# batsim.net
KiCad netlist of a schematic drawn in EAGLE
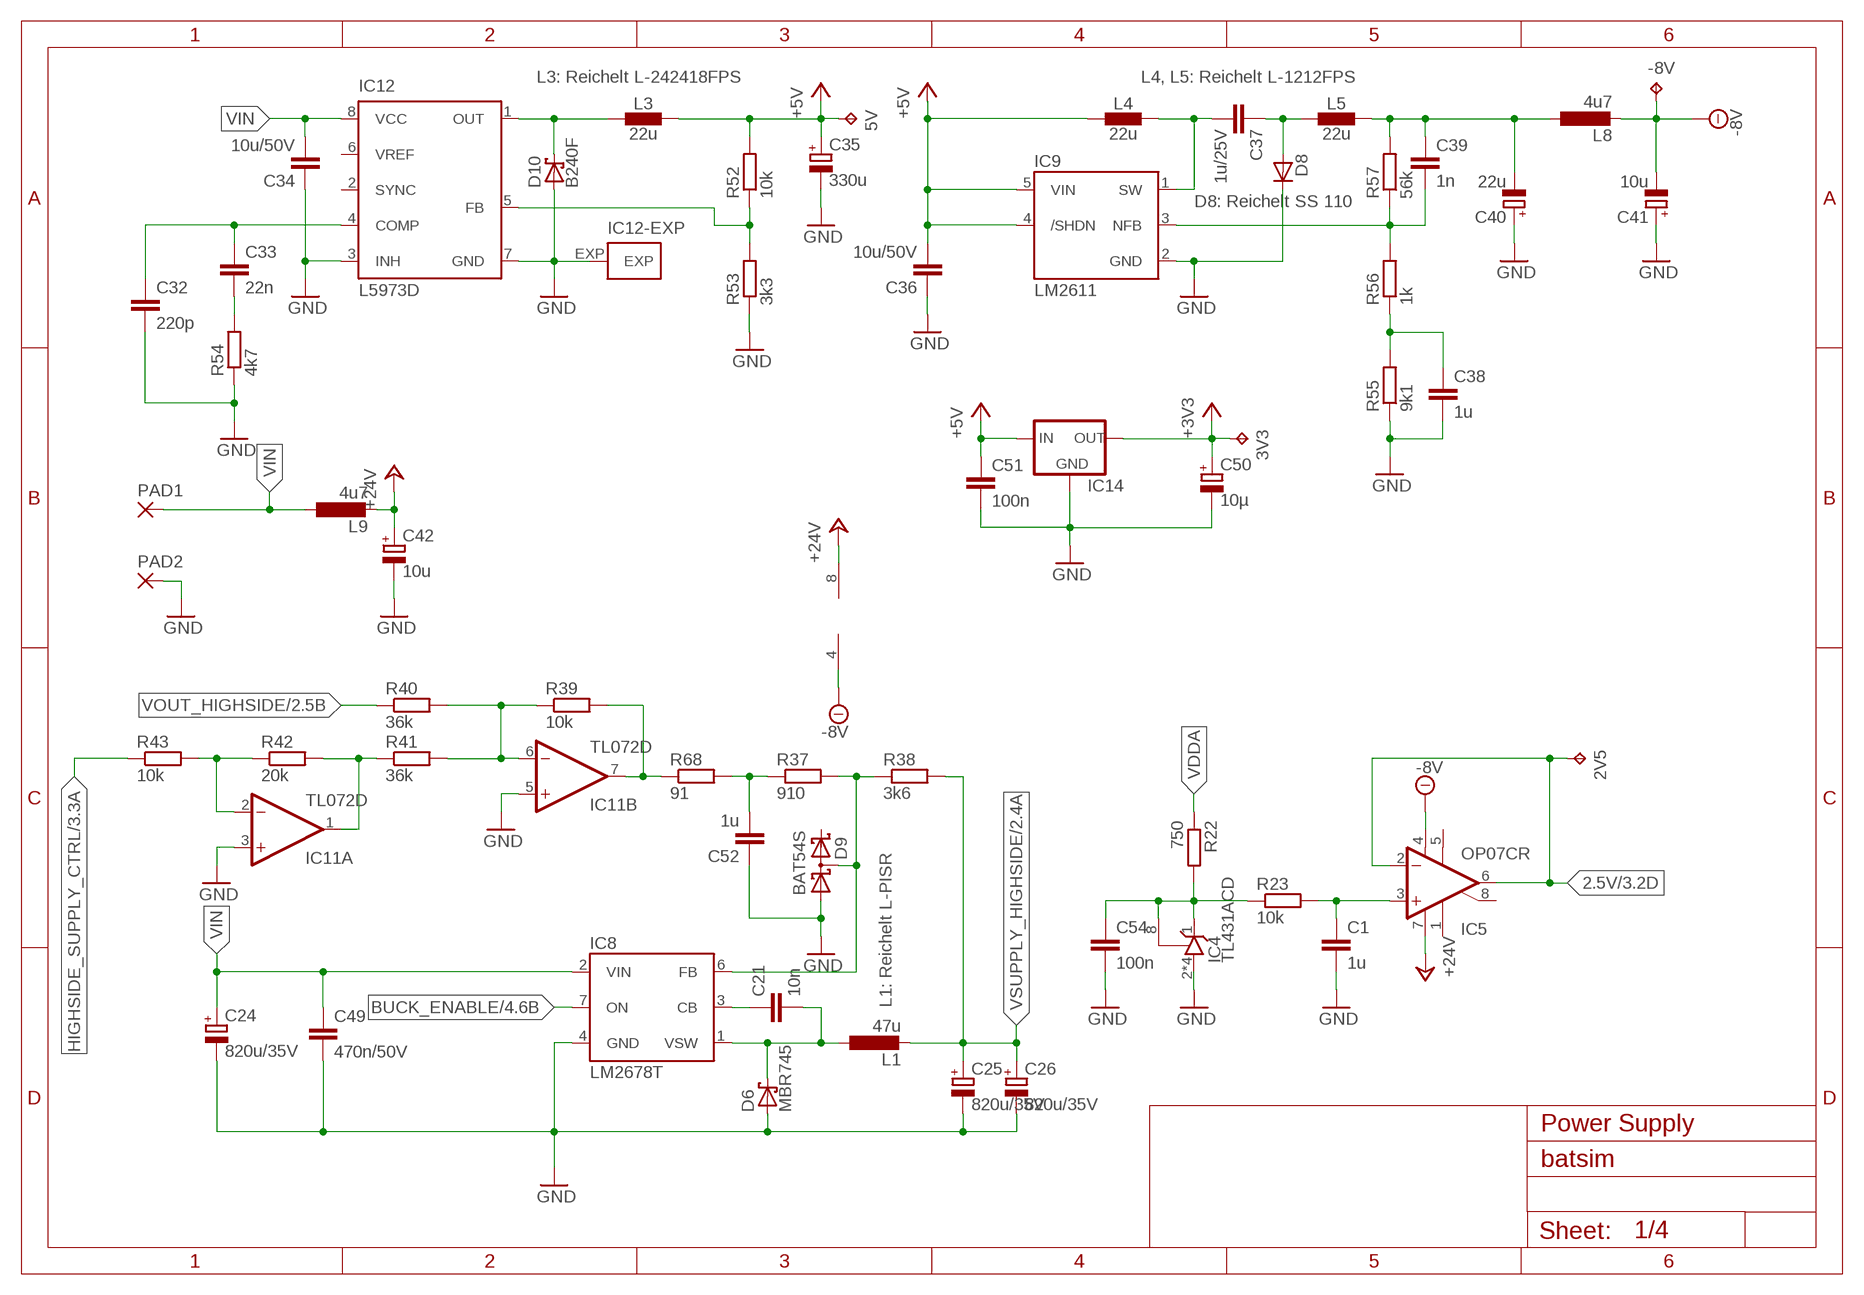
[diagram p0: schematic, sheet 1]
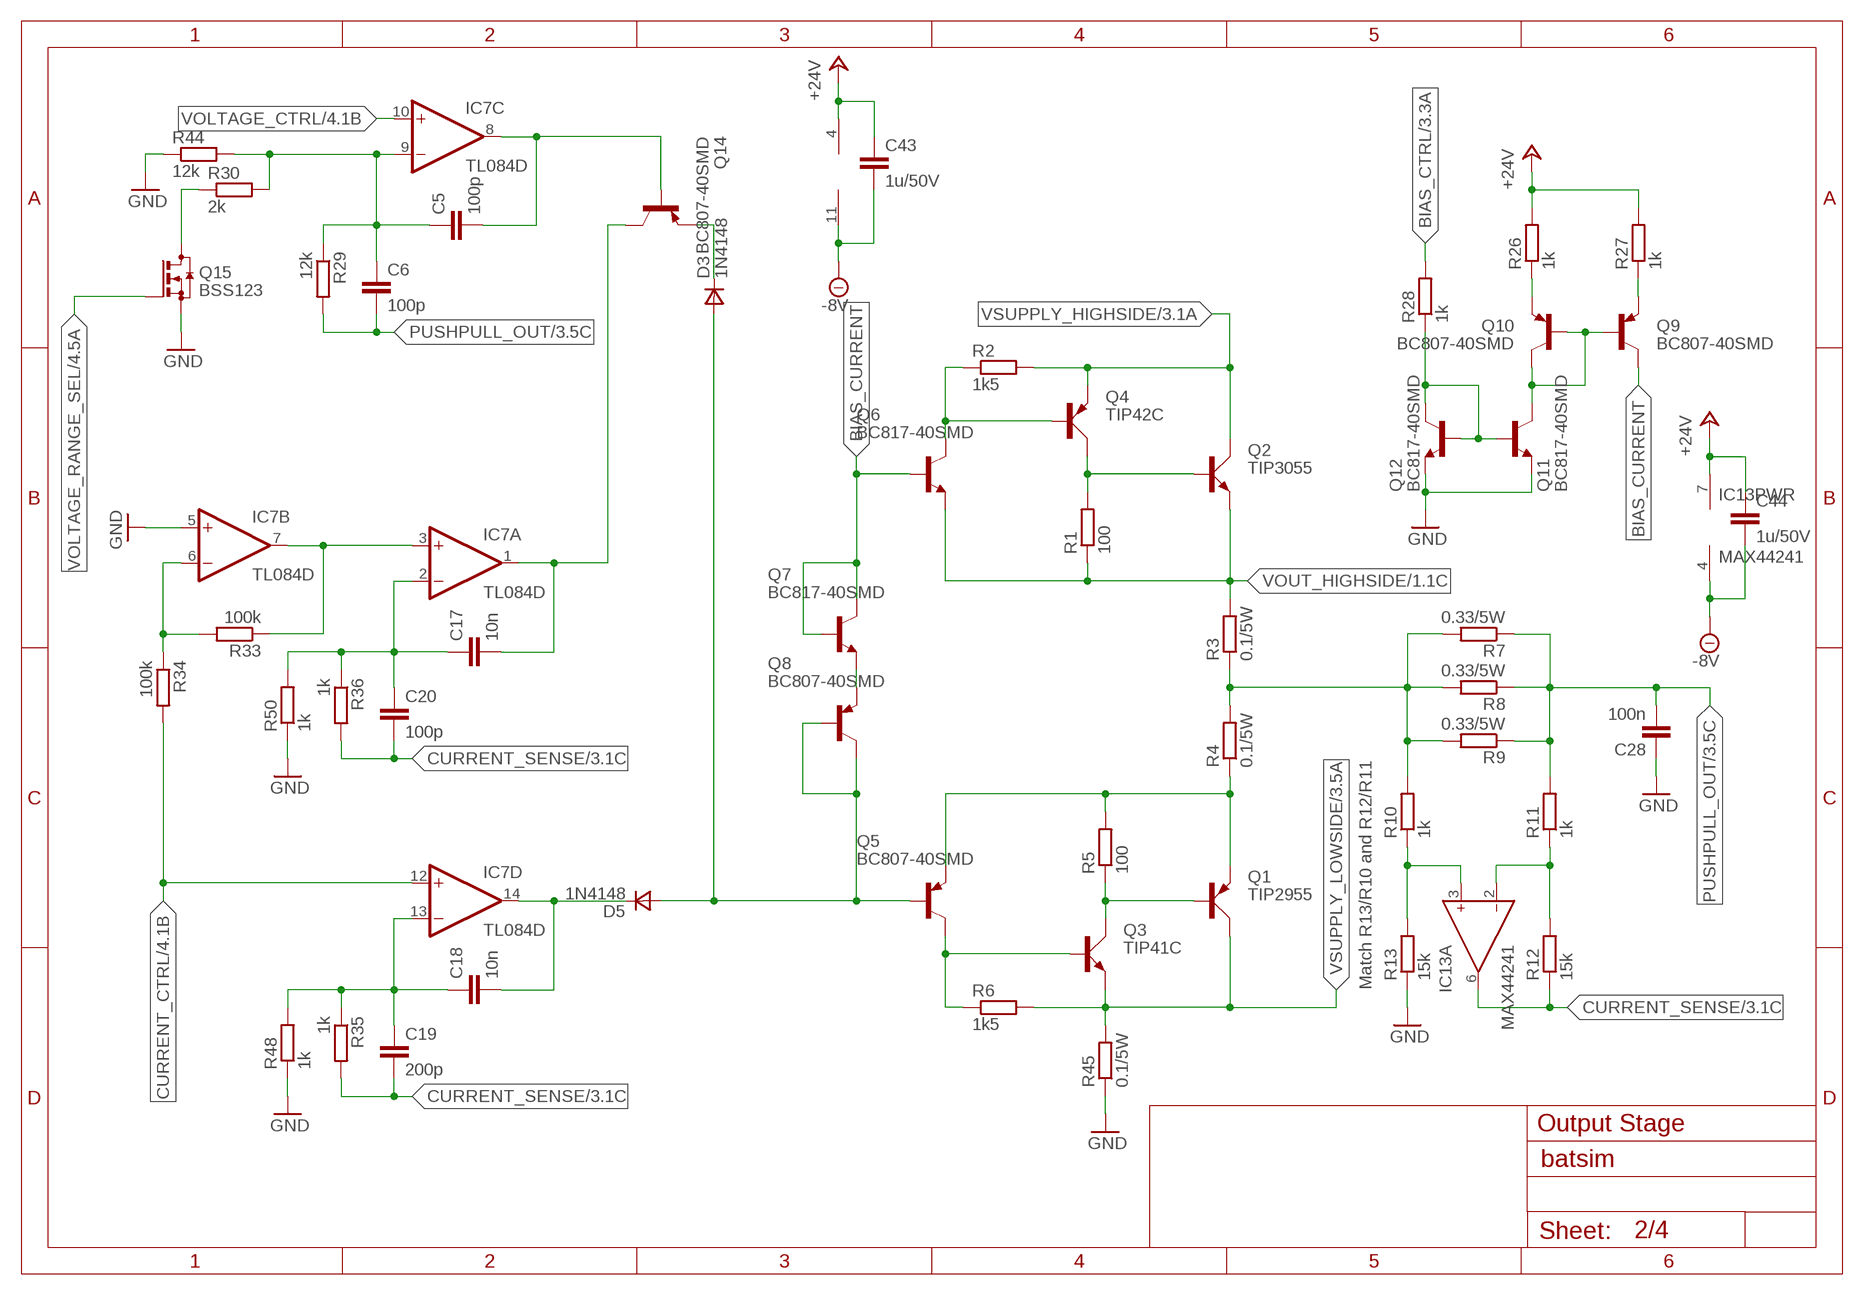
[diagram p1: schematic, sheet 2]
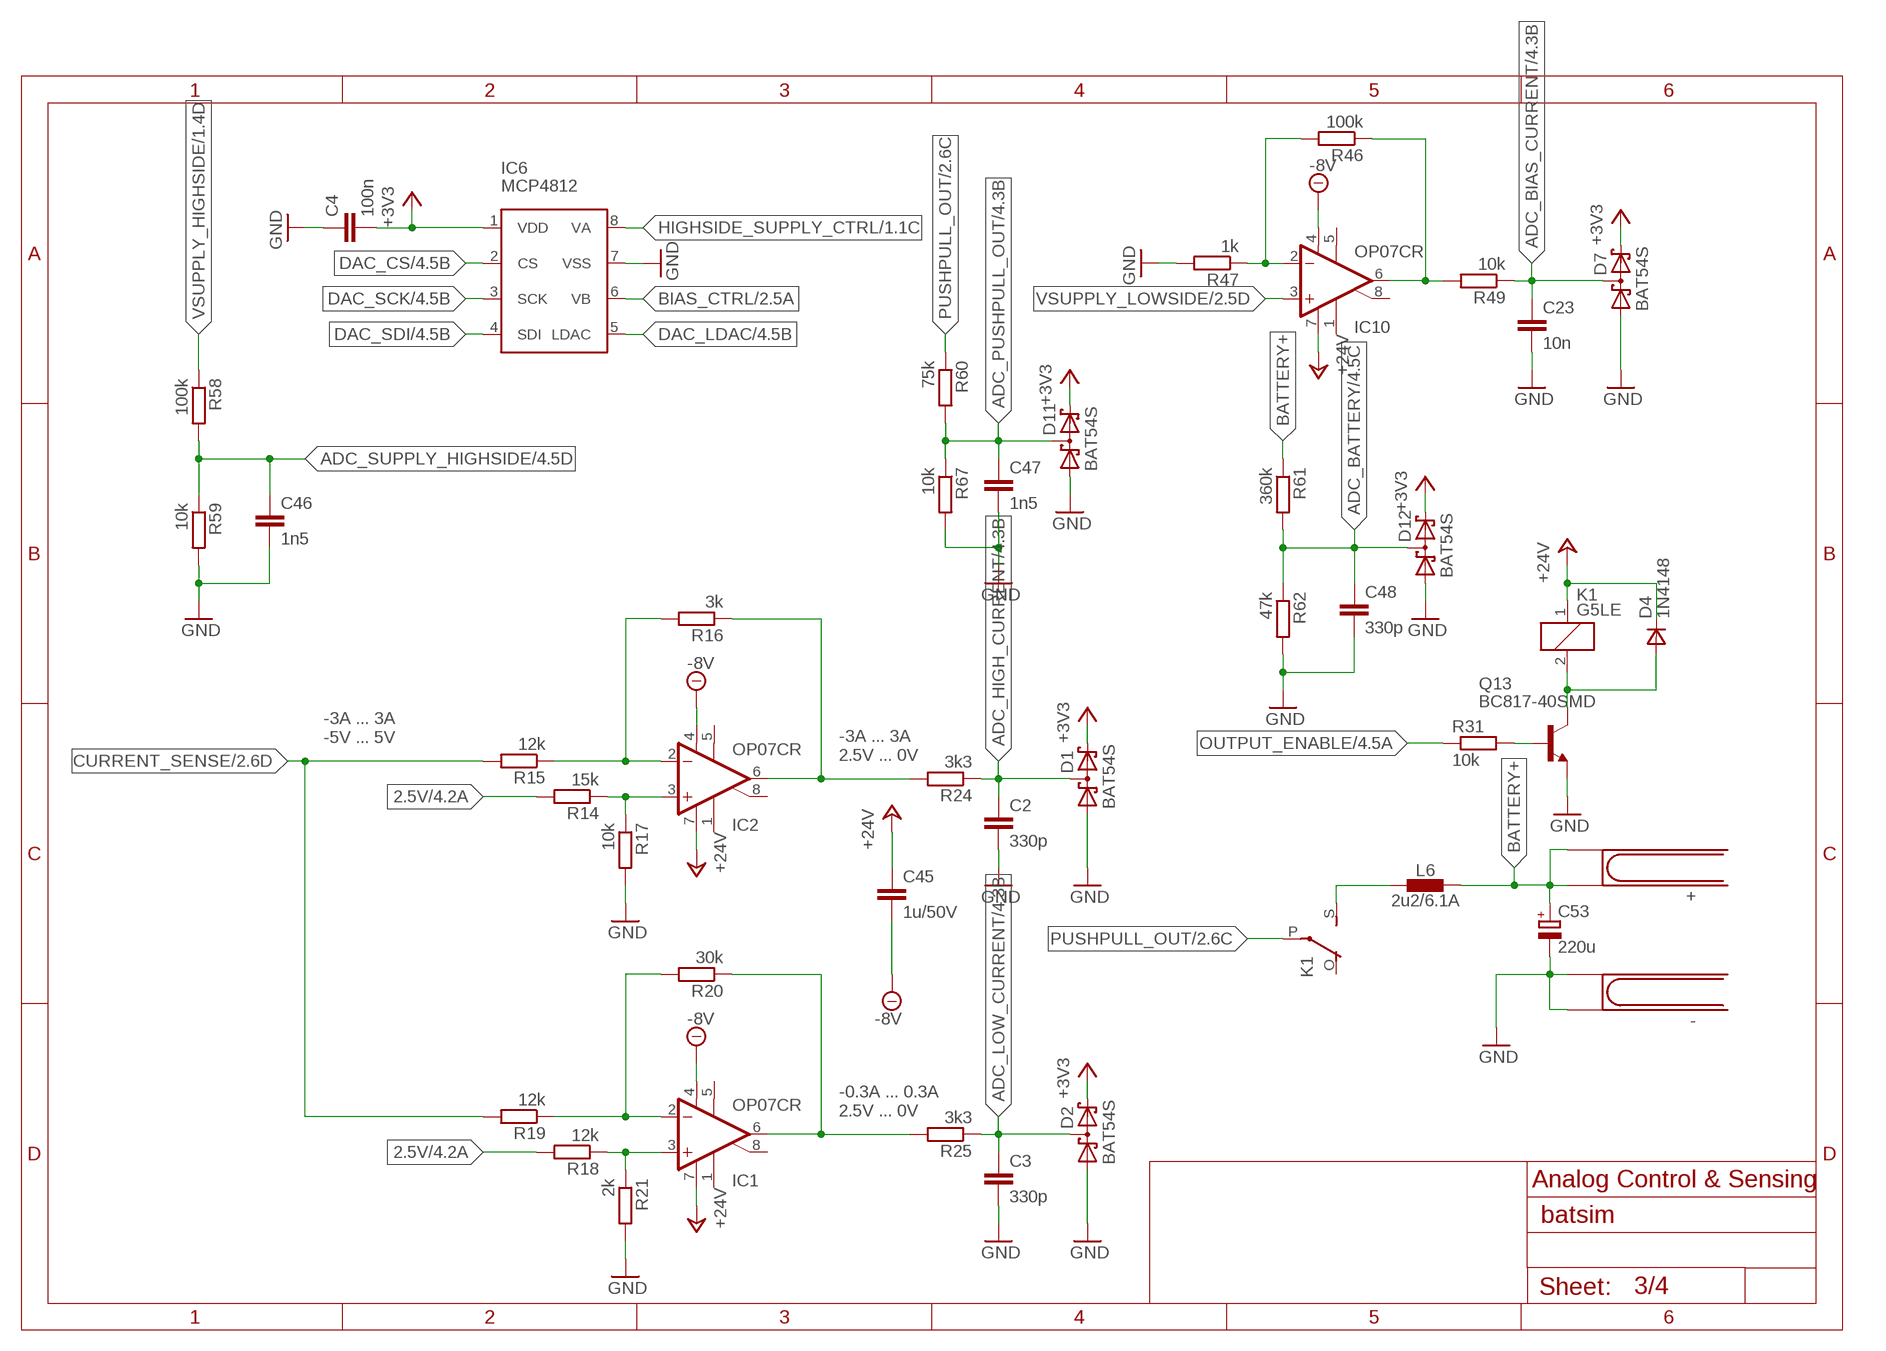
[diagram p2: schematic, sheet 3]
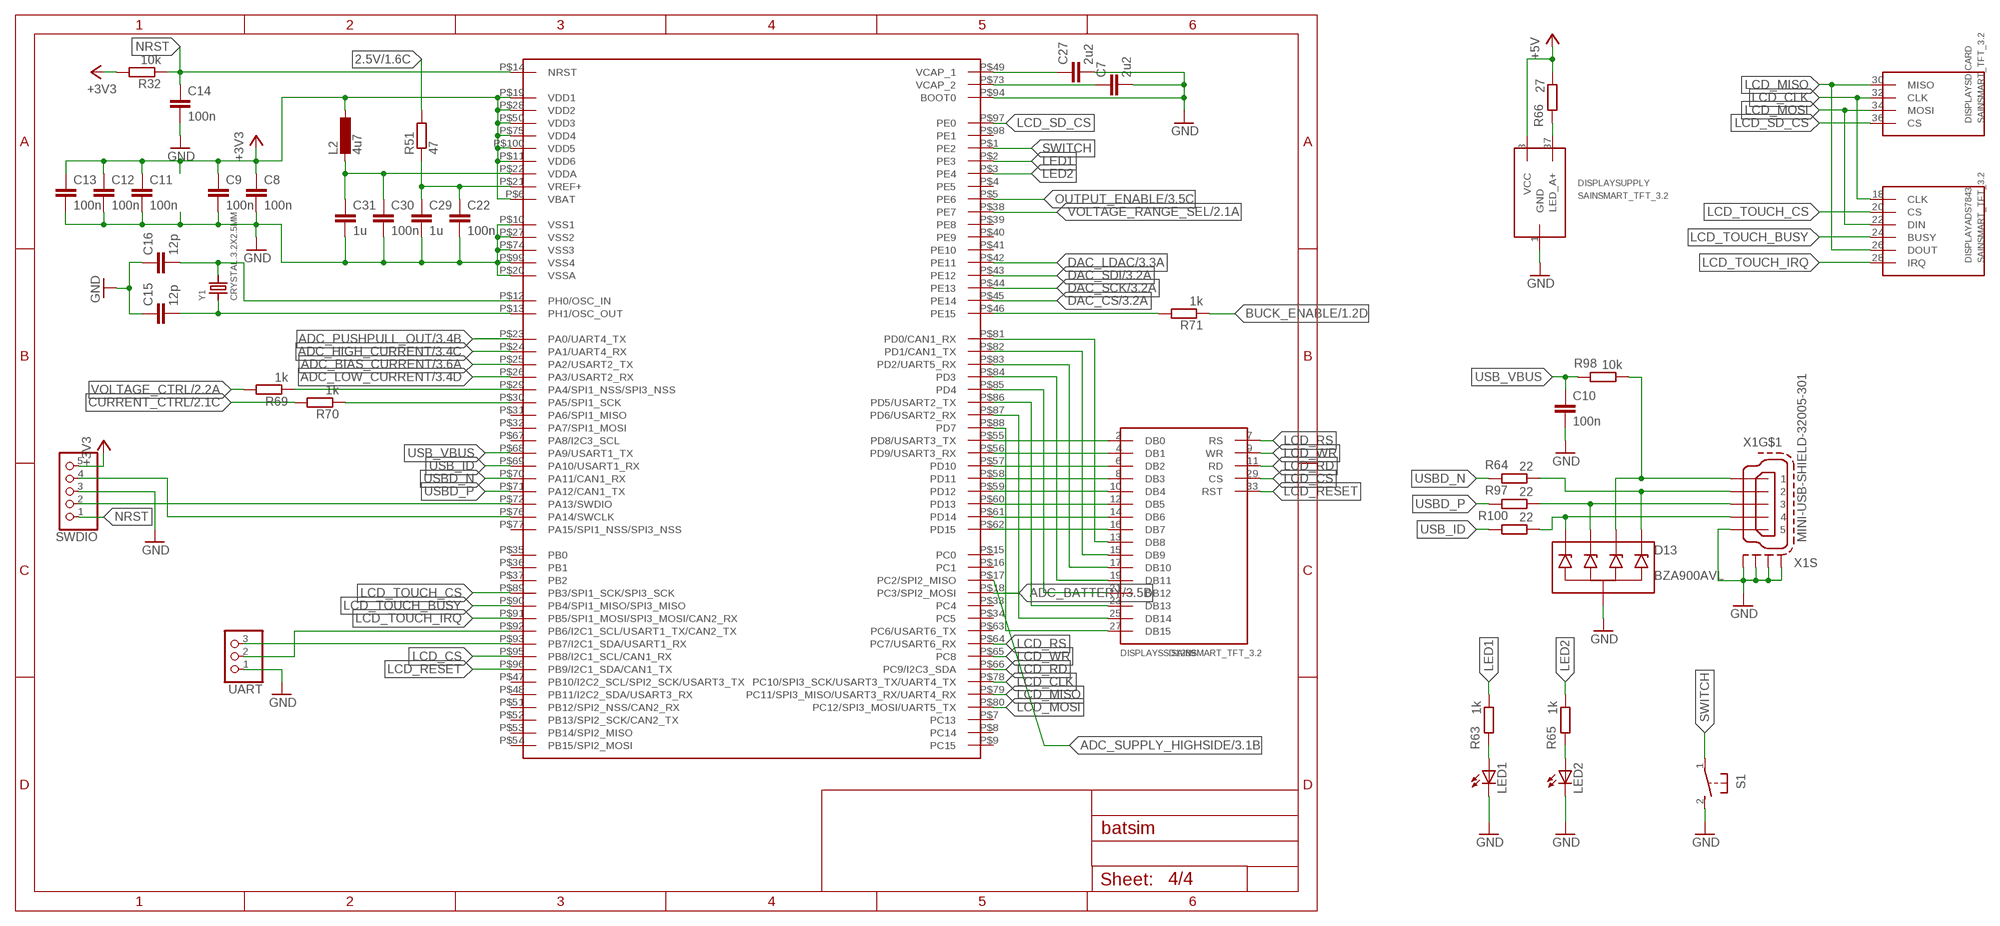
[diagram p3: schematic, sheet 4]

(export (version "E")
  (design (tool "Eeschema 10.0.6"))
  (components
    (comp (ref "C7")
      (value "2u2")
      (footprint "eagle-import:C1206")
      (libsource (lib "eagle-import") (part "C-EUC1206"))
    )
    (comp (ref "C8")
      (value "100n")
      (footprint "eagle-import:C0603")
      (libsource (lib "eagle-import") (part "C-EUC0603"))
    )
    (comp (ref "C9")
      (value "100n")
      (footprint "eagle-import:C0603")
      (libsource (lib "eagle-import") (part "C-EUC0603"))
    )
    (comp (ref "C10")
      (value "100n")
      (footprint "eagle-import:C0603K")
      (libsource (lib "eagle-import") (part "C-EUC0603K"))
    )
    (comp (ref "C11")
      (value "100n")
      (footprint "eagle-import:C0603")
      (libsource (lib "eagle-import") (part "C-EUC0603"))
    )
    (comp (ref "C12")
      (value "100n")
      (footprint "eagle-import:C0603")
      (libsource (lib "eagle-import") (part "C-EUC0603"))
    )
    (comp (ref "C13")
      (value "100n")
      (footprint "eagle-import:C0603")
      (libsource (lib "eagle-import") (part "C-EUC0603"))
    )
    (comp (ref "C14")
      (value "100n")
      (footprint "eagle-import:C0603")
      (libsource (lib "eagle-import") (part "C-EUC0603"))
    )
    (comp (ref "C15")
      (value "12p")
      (footprint "eagle-import:C0603")
      (libsource (lib "eagle-import") (part "C-EUC0603"))
    )
    (comp (ref "C16")
      (value "12p")
      (footprint "eagle-import:C0603")
      (libsource (lib "eagle-import") (part "C-EUC0603"))
    )
    (comp (ref "C22")
      (value "100n")
      (footprint "eagle-import:C0603")
      (libsource (lib "eagle-import") (part "C-EUC0603"))
    )
    (comp (ref "C27")
      (value "2u2")
      (footprint "eagle-import:C1206")
      (libsource (lib "eagle-import") (part "C-EUC1206"))
    )
    (comp (ref "C29")
      (value "1u")
      (footprint "eagle-import:C0603")
      (libsource (lib "eagle-import") (part "C-EUC0603"))
    )
    (comp (ref "C30")
      (value "100n")
      (footprint "eagle-import:C0603")
      (libsource (lib "eagle-import") (part "C-EUC0603"))
    )
    (comp (ref "C31")
      (value "1u")
      (footprint "eagle-import:C0603")
      (libsource (lib "eagle-import") (part "C-EUC0603"))
    )
    (comp (ref "D13")
      (value "BZA900AVL")
      (footprint "eagle-import:SOT-665")
      (libsource (lib "eagle-import") (part "BZA900AVL"))
    )
    (comp (ref "DISPLAY")
      (value "SAINSMART_TFT_3.2")
      (footprint "eagle-import:SAINSMART_TFT_3.2")
      (libsource (lib "eagle-import") (part "SAINSMART_TFT_3.2"))
    )
    (comp (ref "L2")
      (value "4u7")
      (footprint "eagle-import:L2012C")
      (libsource (lib "eagle-import") (part "L-EUL2012C"))
    )
    (comp (ref "LED1")
      (value "LEDCHIP-LED0603")
      (footprint "eagle-import:CHIP-LED0603")
      (libsource (lib "eagle-import") (part "LEDCHIP-LED0603"))
    )
    (comp (ref "LED2")
      (value "LEDCHIP-LED0603")
      (footprint "eagle-import:CHIP-LED0603")
      (libsource (lib "eagle-import") (part "LEDCHIP-LED0603"))
    )
    (comp (ref "R32")
      (value "10k")
      (footprint "eagle-import:R0603")
      (libsource (lib "eagle-import") (part "R-EU_R0603"))
    )
    (comp (ref "R51")
      (value "47")
      (footprint "eagle-import:R0603")
      (libsource (lib "eagle-import") (part "R-EU_R0603"))
    )
    (comp (ref "R63")
      (value "1k")
      (footprint "eagle-import:R0603")
      (libsource (lib "eagle-import") (part "R-EU_R0603"))
    )
    (comp (ref "R64")
      (value "22")
      (footprint "eagle-import:R0603")
      (libsource (lib "eagle-import") (part "R-EU_R0603"))
    )
    (comp (ref "R65")
      (value "1k")
      (footprint "eagle-import:R0603")
      (libsource (lib "eagle-import") (part "R-EU_R0603"))
    )
    (comp (ref "R66")
      (value "27")
      (footprint "eagle-import:R0603")
      (libsource (lib "eagle-import") (part "R-EU_R0603"))
    )
    (comp (ref "R69")
      (value "1k")
      (footprint "eagle-import:R0603")
      (libsource (lib "eagle-import") (part "R-EU_R0603"))
    )
    (comp (ref "R70")
      (value "1k")
      (footprint "eagle-import:R0603")
      (libsource (lib "eagle-import") (part "R-EU_R0603"))
    )
    (comp (ref "R71")
      (value "1k")
      (footprint "eagle-import:R0603")
      (libsource (lib "eagle-import") (part "R-EU_R0603"))
    )
    (comp (ref "R97")
      (value "22")
      (footprint "eagle-import:R0603")
      (libsource (lib "eagle-import") (part "R-EU_R0603"))
    )
    (comp (ref "R98")
      (value "10k")
      (footprint "eagle-import:R0603")
      (libsource (lib "eagle-import") (part "R-EU_R0603"))
    )
    (comp (ref "R100")
      (value "22")
      (footprint "eagle-import:R0603")
      (libsource (lib "eagle-import") (part "R-EU_R0603"))
    )
    (comp (ref "S1")
      (value "31-XX")
      (footprint "eagle-import:B3F-31XX")
      (fields (field (name "MPN") "B3F-3100"))
      (libsource (lib "eagle-import") (part "31-XX"))
    )
    (comp (ref "SWDIO")
      (value "PINHD-1X5")
      (footprint "eagle-import:1X05")
      (libsource (lib "eagle-import") (part "PINHD-1X5"))
    )
    (comp (ref "U$1")
      (value "STM32F407X100")
      (footprint "eagle-import:LQFP100_14")
      (libsource (lib "eagle-import") (part "STM32F407X100"))
    )
    (comp (ref "UART")
      (value "PINHD-1X3")
      (footprint "eagle-import:1X03")
      (libsource (lib "eagle-import") (part "PINHD-1X3"))
    )
    (comp (ref "X1")
      (value "MINI-USB-SHIELD-32005-301")
      (footprint "eagle-import:32005-301")
      (libsource (lib "eagle-import") (part "MINI-USB-SCHIELD-32005-301"))
    )
    (comp (ref "Y1")
      (value "CRYSTAL.3.2X2.5MM")
      (footprint "eagle-import:3.2X2.5MM")
      (libsource (lib "eagle-import") (part "CRYSTAL.3.2X2.5MM"))
    )
    (comp (ref "C5")
      (value "100p")
      (footprint "eagle-import:C0603")
      (libsource (lib "eagle-import") (part "C-EUC0603"))
    )
    (comp (ref "C6")
      (value "100p")
      (footprint "eagle-import:C0603")
      (libsource (lib "eagle-import") (part "C-EUC0603"))
    )
    (comp (ref "C17")
      (value "10n")
      (footprint "eagle-import:C0603")
      (libsource (lib "eagle-import") (part "C-EUC0603"))
    )
    (comp (ref "C18")
      (value "10n")
      (footprint "eagle-import:C0603")
      (libsource (lib "eagle-import") (part "C-EUC0603"))
    )
    (comp (ref "C19")
      (value "200p")
      (footprint "eagle-import:C0603")
      (libsource (lib "eagle-import") (part "C-EUC0603"))
    )
    (comp (ref "C20")
      (value "100p")
      (footprint "eagle-import:C0603")
      (libsource (lib "eagle-import") (part "C-EUC0603"))
    )
    (comp (ref "C28")
      (value "100n")
      (footprint "eagle-import:C1206")
      (libsource (lib "eagle-import") (part "C-EUC1206"))
    )
    (comp (ref "C43")
      (value "1u/50V")
      (footprint "eagle-import:C0603")
      (libsource (lib "eagle-import") (part "C-EUC0603"))
    )
    (comp (ref "C44")
      (value "1u/50V")
      (footprint "eagle-import:C0603")
      (libsource (lib "eagle-import") (part "C-EUC0603"))
    )
    (comp (ref "D3")
      (value "1N4148")
      (footprint "eagle-import:SOD323")
      (fields (field (name "MPN") "CDSOD323-T05C"))
      (libsource (lib "eagle-import") (part "DSOD323"))
    )
    (comp (ref "D5")
      (value "1N4148")
      (footprint "eagle-import:SOD323")
      (fields (field (name "MPN") "CDSOD323-T05C"))
      (libsource (lib "eagle-import") (part "DSOD323"))
    )
    (comp (ref "IC7")
      (value "TL084D")
      (footprint "eagle-import:SO14")
      (libsource (lib "eagle-import") (part "TL084D"))
    )
    (comp (ref "IC13")
      (value "MAX44241")
      (footprint "eagle-import:UMAX8")
      (libsource (lib "eagle-import") (part "MAX44241"))
    )
    (comp (ref "Q1")
      (value "TIP2955")
      (footprint "eagle-import:TOP3AV")
      (libsource (lib "eagle-import") (part "TIP2955"))
    )
    (comp (ref "Q2")
      (value "TIP3055")
      (footprint "eagle-import:TOP3AV")
      (libsource (lib "eagle-import") (part "TIP3055"))
    )
    (comp (ref "Q3")
      (value "TIP41C")
      (footprint "eagle-import:TO220AV")
      (libsource (lib "eagle-import") (part "TIP41C"))
    )
    (comp (ref "Q4")
      (value "TIP42C")
      (footprint "eagle-import:TO220AV")
      (libsource (lib "eagle-import") (part "TIP42C"))
    )
    (comp (ref "Q5")
      (value "BC807-40SMD")
      (footprint "eagle-import:SOT23-BEC")
      (libsource (lib "eagle-import") (part "BC807SMD-40"))
    )
    (comp (ref "Q6")
      (value "BC817-40SMD")
      (footprint "eagle-import:SOT23-BEC")
      (libsource (lib "eagle-import") (part "BC817SMD-40"))
    )
    (comp (ref "Q7")
      (value "BC817-40SMD")
      (footprint "eagle-import:SOT23-BEC")
      (libsource (lib "eagle-import") (part "BC817SMD-40"))
    )
    (comp (ref "Q8")
      (value "BC807-40SMD")
      (footprint "eagle-import:SOT23-BEC")
      (libsource (lib "eagle-import") (part "BC807SMD-40"))
    )
    (comp (ref "Q9")
      (value "BC807-40SMD")
      (footprint "eagle-import:SOT23-BEC")
      (libsource (lib "eagle-import") (part "BC807SMD-40"))
    )
    (comp (ref "Q10")
      (value "BC807-40SMD")
      (footprint "eagle-import:SOT23-BEC")
      (libsource (lib "eagle-import") (part "BC807SMD-40"))
    )
    (comp (ref "Q11")
      (value "BC817-40SMD")
      (footprint "eagle-import:SOT23-BEC")
      (libsource (lib "eagle-import") (part "BC817SMD-40"))
    )
    (comp (ref "Q12")
      (value "BC817-40SMD")
      (footprint "eagle-import:SOT23-BEC")
      (libsource (lib "eagle-import") (part "BC817SMD-40"))
    )
    (comp (ref "Q14")
      (value "BC807-40SMD")
      (footprint "eagle-import:SOT23-BEC")
      (libsource (lib "eagle-import") (part "BC807SMD-40"))
    )
    (comp (ref "Q15")
      (value "BSS123")
      (footprint "eagle-import:SOT23")
      (libsource (lib "eagle-import") (part "BSS123"))
    )
    (comp (ref "R1")
      (value "100")
      (footprint "eagle-import:R0603")
      (libsource (lib "eagle-import") (part "R-EU_R0603"))
    )
    (comp (ref "R2")
      (value "1k5")
      (footprint "eagle-import:R0603")
      (libsource (lib "eagle-import") (part "R-EU_R0603"))
    )
    (comp (ref "R3")
      (value "0.1/5W")
      (footprint "eagle-import:5WAXIAL")
      (libsource (lib "eagle-import") (part "5WAXIAL"))
    )
    (comp (ref "R4")
      (value "0.1/5W")
      (footprint "eagle-import:5WAXIAL")
      (libsource (lib "eagle-import") (part "5WAXIAL"))
    )
    (comp (ref "R5")
      (value "100")
      (footprint "eagle-import:R0603")
      (libsource (lib "eagle-import") (part "R-EU_R0603"))
    )
    (comp (ref "R6")
      (value "1k5")
      (footprint "eagle-import:R0603")
      (libsource (lib "eagle-import") (part "R-EU_R0603"))
    )
    (comp (ref "R7")
      (value "0.33/5W")
      (footprint "eagle-import:5WAXIAL")
      (libsource (lib "eagle-import") (part "5WAXIAL"))
    )
    (comp (ref "R8")
      (value "0.33/5W")
      (footprint "eagle-import:5WAXIAL")
      (libsource (lib "eagle-import") (part "5WAXIAL"))
    )
    (comp (ref "R9")
      (value "0.33/5W")
      (footprint "eagle-import:5WAXIAL")
      (libsource (lib "eagle-import") (part "5WAXIAL"))
    )
    (comp (ref "R10")
      (value "1k")
      (footprint "eagle-import:R0603")
      (libsource (lib "eagle-import") (part "R-EU_R0603"))
    )
    (comp (ref "R11")
      (value "1k")
      (footprint "eagle-import:R0603")
      (libsource (lib "eagle-import") (part "R-EU_R0603"))
    )
    (comp (ref "R12")
      (value "15k")
      (footprint "eagle-import:R0603")
      (libsource (lib "eagle-import") (part "R-EU_R0603"))
    )
    (comp (ref "R13")
      (value "15k")
      (footprint "eagle-import:R0603")
      (libsource (lib "eagle-import") (part "R-EU_R0603"))
    )
    (comp (ref "R26")
      (value "1k")
      (footprint "eagle-import:R0603")
      (libsource (lib "eagle-import") (part "R-EU_R0603"))
    )
    (comp (ref "R27")
      (value "1k")
      (footprint "eagle-import:R0603")
      (libsource (lib "eagle-import") (part "R-EU_R0603"))
    )
    (comp (ref "R28")
      (value "1k")
      (footprint "eagle-import:R0603")
      (libsource (lib "eagle-import") (part "R-EU_R0603"))
    )
    (comp (ref "R29")
      (value "12k")
      (footprint "eagle-import:R0603")
      (libsource (lib "eagle-import") (part "R-EU_R0603"))
    )
    (comp (ref "R30")
      (value "2k")
      (footprint "eagle-import:R0603")
      (libsource (lib "eagle-import") (part "R-EU_R0603"))
    )
    (comp (ref "R33")
      (value "100k")
      (footprint "eagle-import:R0603")
      (libsource (lib "eagle-import") (part "R-EU_R0603"))
    )
    (comp (ref "R34")
      (value "100k")
      (footprint "eagle-import:R0603")
      (libsource (lib "eagle-import") (part "R-EU_R0603"))
    )
    (comp (ref "R35")
      (value "1k")
      (footprint "eagle-import:R0603")
      (libsource (lib "eagle-import") (part "R-EU_R0603"))
    )
    (comp (ref "R36")
      (value "1k")
      (footprint "eagle-import:R0603")
      (libsource (lib "eagle-import") (part "R-EU_R0603"))
    )
    (comp (ref "R44")
      (value "12k")
      (footprint "eagle-import:R0603")
      (libsource (lib "eagle-import") (part "R-EU_R0603"))
    )
    (comp (ref "R45")
      (value "0.1/5W")
      (footprint "eagle-import:5WAXIAL")
      (libsource (lib "eagle-import") (part "5WAXIAL"))
    )
    (comp (ref "R48")
      (value "1k")
      (footprint "eagle-import:R0603")
      (libsource (lib "eagle-import") (part "R-EU_R0603"))
    )
    (comp (ref "R50")
      (value "1k")
      (footprint "eagle-import:R0603")
      (libsource (lib "eagle-import") (part "R-EU_R0603"))
    )
    (comp (ref "+")
      (value "4MMJACK")
      (footprint "eagle-import:4MMJACK")
      (libsource (lib "eagle-import") (part "4MMJACK"))
    )
    (comp (ref "-")
      (value "4MMJACK")
      (footprint "eagle-import:4MMJACK")
      (libsource (lib "eagle-import") (part "4MMJACK"))
    )
    (comp (ref "C2")
      (value "330p")
      (footprint "eagle-import:C0603")
      (libsource (lib "eagle-import") (part "C-EUC0603"))
    )
    (comp (ref "C3")
      (value "330p")
      (footprint "eagle-import:C0603")
      (libsource (lib "eagle-import") (part "C-EUC0603"))
    )
    (comp (ref "C4")
      (value "100n")
      (footprint "eagle-import:C0603")
      (libsource (lib "eagle-import") (part "C-EUC0603"))
    )
    (comp (ref "C23")
      (value "10n")
      (footprint "eagle-import:C0603")
      (libsource (lib "eagle-import") (part "C-EUC0603"))
    )
    (comp (ref "C45")
      (value "1u/50V")
      (footprint "eagle-import:C0603")
      (libsource (lib "eagle-import") (part "C-EUC0603"))
    )
    (comp (ref "C46")
      (value "1n5")
      (footprint "eagle-import:C0603")
      (libsource (lib "eagle-import") (part "C-EUC0603"))
    )
    (comp (ref "C47")
      (value "1n5")
      (footprint "eagle-import:C0603")
      (libsource (lib "eagle-import") (part "C-EUC0603"))
    )
    (comp (ref "C48")
      (value "330p")
      (footprint "eagle-import:C0603")
      (libsource (lib "eagle-import") (part "C-EUC0603"))
    )
    (comp (ref "C53")
      (value "220u")
      (footprint "eagle-import:E5-10,5")
      (libsource (lib "eagle-import") (part "resistor_CPOL-EUE5-10.5"))
    )
    (comp (ref "D1")
      (value "BAT54S")
      (footprint "eagle-import:SOT23")
      (libsource (lib "eagle-import") (part "BAT54S"))
    )
    (comp (ref "D2")
      (value "BAT54S")
      (footprint "eagle-import:SOT23")
      (libsource (lib "eagle-import") (part "BAT54S"))
    )
    (comp (ref "D4")
      (value "1N4148")
      (footprint "eagle-import:SOD323")
      (fields (field (name "MPN") "CDSOD323-T05C"))
      (libsource (lib "eagle-import") (part "DSOD323"))
    )
    (comp (ref "D7")
      (value "BAT54S")
      (footprint "eagle-import:SOT23")
      (libsource (lib "eagle-import") (part "BAT54S"))
    )
    (comp (ref "D11")
      (value "BAT54S")
      (footprint "eagle-import:SOT23")
      (libsource (lib "eagle-import") (part "BAT54S"))
    )
    (comp (ref "D12")
      (value "BAT54S")
      (footprint "eagle-import:SOT23")
      (libsource (lib "eagle-import") (part "BAT54S"))
    )
    (comp (ref "IC1")
      (value "OP07CR")
      (footprint "eagle-import:SO08")
      (libsource (lib "eagle-import") (part "OP07RC"))
    )
    (comp (ref "IC2")
      (value "OP07CR")
      (footprint "eagle-import:SO08")
      (libsource (lib "eagle-import") (part "OP07RC"))
    )
    (comp (ref "IC6")
      (value "MCP4812")
      (footprint "eagle-import:SO08")
      (fields (field (name "MPN") "MCP4822-E/SN"))
      (libsource (lib "eagle-import") (part "MCP4812"))
    )
    (comp (ref "IC10")
      (value "OP07CR")
      (footprint "eagle-import:SO08")
      (libsource (lib "eagle-import") (part "OP07RC"))
    )
    (comp (ref "K1")
      (value "G5LE")
      (footprint "eagle-import:G5LE")
      (libsource (lib "eagle-import") (part "G5LE"))
    )
    (comp (ref "L6")
      (value "2u2/6.1A")
      (footprint "eagle-import:L_NR60XX")
      (libsource (lib "eagle-import") (part "INDUCTOR-NR60XX"))
    )
    (comp (ref "Q13")
      (value "BC817-40SMD")
      (footprint "eagle-import:SOT23-BEC")
      (libsource (lib "eagle-import") (part "BC817SMD-40"))
    )
    (comp (ref "R14")
      (value "15k")
      (footprint "eagle-import:R0603")
      (libsource (lib "eagle-import") (part "R-EU_R0603"))
    )
    (comp (ref "R15")
      (value "12k")
      (footprint "eagle-import:R0603")
      (libsource (lib "eagle-import") (part "R-EU_R0603"))
    )
    (comp (ref "R16")
      (value "3k")
      (footprint "eagle-import:R0603")
      (libsource (lib "eagle-import") (part "R-EU_R0603"))
    )
    (comp (ref "R17")
      (value "10k")
      (footprint "eagle-import:R0603")
      (libsource (lib "eagle-import") (part "R-EU_R0603"))
    )
    (comp (ref "R18")
      (value "12k")
      (footprint "eagle-import:R0603")
      (libsource (lib "eagle-import") (part "R-EU_R0603"))
    )
    (comp (ref "R19")
      (value "12k")
      (footprint "eagle-import:R0603")
      (libsource (lib "eagle-import") (part "R-EU_R0603"))
    )
    (comp (ref "R20")
      (value "30k")
      (footprint "eagle-import:R0603")
      (libsource (lib "eagle-import") (part "R-EU_R0603"))
    )
    (comp (ref "R21")
      (value "2k")
      (footprint "eagle-import:R0603")
      (libsource (lib "eagle-import") (part "R-EU_R0603"))
    )
    (comp (ref "R24")
      (value "3k3")
      (footprint "eagle-import:R0603")
      (libsource (lib "eagle-import") (part "R-EU_R0603"))
    )
    (comp (ref "R25")
      (value "3k3")
      (footprint "eagle-import:R0603")
      (libsource (lib "eagle-import") (part "R-EU_R0603"))
    )
    (comp (ref "R31")
      (value "10k")
      (footprint "eagle-import:R0603")
      (libsource (lib "eagle-import") (part "R-EU_R0603"))
    )
    (comp (ref "R46")
      (value "100k")
      (footprint "eagle-import:R0603")
      (libsource (lib "eagle-import") (part "R-EU_R0603"))
    )
    (comp (ref "R47")
      (value "1k")
      (footprint "eagle-import:R0603")
      (libsource (lib "eagle-import") (part "R-EU_R0603"))
    )
    (comp (ref "R49")
      (value "10k")
      (footprint "eagle-import:R0603")
      (libsource (lib "eagle-import") (part "R-EU_R0603"))
    )
    (comp (ref "R58")
      (value "100k")
      (footprint "eagle-import:R0603")
      (libsource (lib "eagle-import") (part "R-EU_R0603"))
    )
    (comp (ref "R59")
      (value "10k")
      (footprint "eagle-import:R0603")
      (libsource (lib "eagle-import") (part "R-EU_R0603"))
    )
    (comp (ref "R60")
      (value "75k")
      (footprint "eagle-import:R0603")
      (libsource (lib "eagle-import") (part "R-EU_R0603"))
    )
    (comp (ref "R61")
      (value "360k")
      (footprint "eagle-import:R0603")
      (libsource (lib "eagle-import") (part "R-EU_R0603"))
    )
    (comp (ref "R62")
      (value "47k")
      (footprint "eagle-import:R0603")
      (libsource (lib "eagle-import") (part "R-EU_R0603"))
    )
    (comp (ref "R67")
      (value "10k")
      (footprint "eagle-import:R0603")
      (libsource (lib "eagle-import") (part "R-EU_R0603"))
    )
    (comp (ref "-8V")
      (value "TPB1,27")
      (footprint "eagle-import:B1,27")
      (libsource (lib "eagle-import") (part "TPB1,27"))
    )
    (comp (ref "2V5")
      (value "TPB1,27")
      (footprint "eagle-import:B1,27")
      (libsource (lib "eagle-import") (part "TPB1,27"))
    )
    (comp (ref "3V3")
      (value "TPB1,27")
      (footprint "eagle-import:B1,27")
      (libsource (lib "eagle-import") (part "TPB1,27"))
    )
    (comp (ref "5V")
      (value "TPB1,27")
      (footprint "eagle-import:B1,27")
      (libsource (lib "eagle-import") (part "TPB1,27"))
    )
    (comp (ref "C1")
      (value "1u")
      (footprint "eagle-import:C0603")
      (libsource (lib "eagle-import") (part "C-EUC0603"))
    )
    (comp (ref "C21")
      (value "10n")
      (footprint "eagle-import:C0603")
      (libsource (lib "eagle-import") (part "C-EUC0603"))
    )
    (comp (ref "C24")
      (value "820u/35V")
      (footprint "eagle-import:E5-10,5")
      (libsource (lib "eagle-import") (part "resistor_CPOL-EUE5-10.5"))
    )
    (comp (ref "C25")
      (value "820u/35V")
      (footprint "eagle-import:E5-10,5")
      (libsource (lib "eagle-import") (part "resistor_CPOL-EUE5-10.5"))
    )
    (comp (ref "C26")
      (value "820u/35V")
      (footprint "eagle-import:E5-10,5")
      (libsource (lib "eagle-import") (part "resistor_CPOL-EUE5-10.5"))
    )
    (comp (ref "C32")
      (value "220p")
      (footprint "eagle-import:C0603")
      (libsource (lib "eagle-import") (part "C-EUC0603"))
    )
    (comp (ref "C33")
      (value "22n")
      (footprint "eagle-import:C0603")
      (libsource (lib "eagle-import") (part "C-EUC0603"))
    )
    (comp (ref "C34")
      (value "10u/50V")
      (footprint "eagle-import:C1206")
      (libsource (lib "eagle-import") (part "C-EUC1206"))
    )
    (comp (ref "C35")
      (value "330u")
      (footprint "eagle-import:153CLV-0605")
      (libsource (lib "eagle-import") (part "resistor_CPOL-EU153CLV-0605"))
    )
    (comp (ref "C36")
      (value "10u/50V")
      (footprint "eagle-import:C1206")
      (libsource (lib "eagle-import") (part "C-EUC1206"))
    )
    (comp (ref "C37")
      (value "1u/25V")
      (footprint "eagle-import:C1206")
      (libsource (lib "eagle-import") (part "C-EUC1206"))
    )
    (comp (ref "C38")
      (value "1u")
      (footprint "eagle-import:C0603")
      (libsource (lib "eagle-import") (part "C-EUC0603"))
    )
    (comp (ref "C39")
      (value "1n")
      (footprint "eagle-import:C0603")
      (libsource (lib "eagle-import") (part "C-EUC0603"))
    )
    (comp (ref "C40")
      (value "22u")
      (footprint "eagle-import:153CLV-0505")
      (libsource (lib "eagle-import") (part "resistor_CPOL-EU153CLV-0505"))
    )
    (comp (ref "C41")
      (value "10u")
      (footprint "eagle-import:153CLV-0405")
      (libsource (lib "eagle-import") (part "resistor_CPOL-EU153CLV-0405"))
    )
    (comp (ref "C42")
      (value "10u")
      (footprint "eagle-import:153CLV-0505")
      (libsource (lib "eagle-import") (part "resistor_CPOL-EU153CLV-0505"))
    )
    (comp (ref "C49")
      (value "470n/50V")
      (footprint "eagle-import:C1206")
      (libsource (lib "eagle-import") (part "C-EUC1206"))
    )
    (comp (ref "C50")
      (value "10µ")
      (footprint "eagle-import:SMC_A")
      (libsource (lib "eagle-import") (part "CPOL-EUSMCA"))
    )
    (comp (ref "C51")
      (value "100n")
      (footprint "eagle-import:C0603")
      (libsource (lib "eagle-import") (part "C-EUC0603"))
    )
    (comp (ref "C52")
      (value "1u")
      (footprint "eagle-import:C0603")
      (libsource (lib "eagle-import") (part "C-EUC0603"))
    )
    (comp (ref "C54")
      (value "100n")
      (footprint "eagle-import:C0603")
      (libsource (lib "eagle-import") (part "C-EUC0603"))
    )
    (comp (ref "D6")
      (value "MBR745")
      (footprint "eagle-import:TO220ACS")
      (libsource (lib "eagle-import") (part "MBR745"))
    )
    (comp (ref "D8")
      (value "D-SMA")
      (footprint "eagle-import:SMA")
      (libsource (lib "eagle-import") (part "D-SMA"))
    )
    (comp (ref "D9")
      (value "BAT54S")
      (footprint "eagle-import:SOT23")
      (libsource (lib "eagle-import") (part "BAT54S"))
    )
    (comp (ref "D10")
      (value "B240F")
      (footprint "eagle-import:SMB")
      (libsource (lib "eagle-import") (part "SCHOTTKY-DIODESMD"))
    )
    (comp (ref "IC4")
      (value "TL431ACD")
      (footprint "eagle-import:SO8")
      (libsource (lib "eagle-import") (part "TL431ACD"))
    )
    (comp (ref "IC5")
      (value "OP07CR")
      (footprint "eagle-import:SO08")
      (libsource (lib "eagle-import") (part "OP07RC"))
    )
    (comp (ref "IC8")
      (value "LM2678T")
      (footprint "eagle-import:TO220-7")
      (libsource (lib "eagle-import") (part "LM2678T"))
    )
    (comp (ref "IC9")
      (value "LM2611")
      (footprint "eagle-import:SOT23-5")
      (libsource (lib "eagle-import") (part "LM2611"))
    )
    (comp (ref "IC11")
      (value "TL072D")
      (footprint "eagle-import:SO08")
      (libsource (lib "eagle-import") (part "TL072D"))
    )
    (comp (ref "IC12")
      (value "L5973D")
      (footprint "eagle-import:HSOP8")
      (fields (field (name "MF") "STMICROELECTRONICS"))
      (libsource (lib "eagle-import") (part "L5973D"))
    )
    (comp (ref "IC14")
      (value "LM1117")
      (footprint "eagle-import:SOT223")
      (libsource (lib "eagle-import") (part "LM1117"))
    )
    (comp (ref "L1")
      (value "47u")
      (footprint "eagle-import:PISR")
      (libsource (lib "eagle-import") (part "L-EUPISR"))
    )
    (comp (ref "L3")
      (value "22u")
      (footprint "eagle-import:L_NR60XX")
      (libsource (lib "eagle-import") (part "INDUCTOR-NR60XX"))
    )
    (comp (ref "L4")
      (value "22u")
      (footprint "eagle-import:L_1212")
      (libsource (lib "eagle-import") (part "INDUCTOR-1212"))
    )
    (comp (ref "L5")
      (value "22u")
      (footprint "eagle-import:L_1212")
      (libsource (lib "eagle-import") (part "INDUCTOR-1212"))
    )
    (comp (ref "L8")
      (value "4u7")
      (footprint "eagle-import:L2012C")
      (libsource (lib "eagle-import") (part "L-EUL2012C"))
    )
    (comp (ref "L9")
      (value "4u7")
      (footprint "eagle-import:L2012C")
      (libsource (lib "eagle-import") (part "L-EUL2012C"))
    )
    (comp (ref "PAD1")
      (value "3,81/1,4")
      (footprint "eagle-import:3,81_1,4")
      (libsource (lib "eagle-import") (part "3,81/1,4"))
    )
    (comp (ref "PAD2")
      (value "3,81/1,4")
      (footprint "eagle-import:3,81_1,4")
      (libsource (lib "eagle-import") (part "3,81/1,4"))
    )
    (comp (ref "R22")
      (value "750")
      (footprint "eagle-import:R0603")
      (libsource (lib "eagle-import") (part "R-EU_R0603"))
    )
    (comp (ref "R23")
      (value "10k")
      (footprint "eagle-import:R0603")
      (libsource (lib "eagle-import") (part "R-EU_R0603"))
    )
    (comp (ref "R37")
      (value "910")
      (footprint "eagle-import:R0603")
      (libsource (lib "eagle-import") (part "R-EU_R0603"))
    )
    (comp (ref "R38")
      (value "3k6")
      (footprint "eagle-import:R0603")
      (libsource (lib "eagle-import") (part "R-EU_R0603"))
    )
    (comp (ref "R39")
      (value "10k")
      (footprint "eagle-import:R0603")
      (libsource (lib "eagle-import") (part "R-EU_R0603"))
    )
    (comp (ref "R40")
      (value "36k")
      (footprint "eagle-import:R0603")
      (libsource (lib "eagle-import") (part "R-EU_R0603"))
    )
    (comp (ref "R41")
      (value "36k")
      (footprint "eagle-import:R0603")
      (libsource (lib "eagle-import") (part "R-EU_R0603"))
    )
    (comp (ref "R42")
      (value "20k")
      (footprint "eagle-import:R0603")
      (libsource (lib "eagle-import") (part "R-EU_R0603"))
    )
    (comp (ref "R43")
      (value "10k")
      (footprint "eagle-import:R0603")
      (libsource (lib "eagle-import") (part "R-EU_R0603"))
    )
    (comp (ref "R52")
      (value "10k")
      (footprint "eagle-import:R0603")
      (libsource (lib "eagle-import") (part "R-EU_R0603"))
    )
    (comp (ref "R53")
      (value "3k3")
      (footprint "eagle-import:R0603")
      (libsource (lib "eagle-import") (part "R-EU_R0603"))
    )
    (comp (ref "R54")
      (value "4k7")
      (footprint "eagle-import:R0603")
      (libsource (lib "eagle-import") (part "R-EU_R0603"))
    )
    (comp (ref "R55")
      (value "9k1")
      (footprint "eagle-import:R0603")
      (libsource (lib "eagle-import") (part "R-EU_R0603"))
    )
    (comp (ref "R56")
      (value "1k")
      (footprint "eagle-import:R0603")
      (libsource (lib "eagle-import") (part "R-EU_R0603"))
    )
    (comp (ref "R57")
      (value "56k")
      (footprint "eagle-import:R0603")
      (libsource (lib "eagle-import") (part "R-EU_R0603"))
    )
    (comp (ref "R68")
      (value "91")
      (footprint "eagle-import:R0603")
      (libsource (lib "eagle-import") (part "R-EU_R0603"))
    )
  )
  (nets
    (net (code "1") (name "+3V3") (class "Default")
      (node (ref "3V3") (pin "TP") (pinfunction "TP_TP") (pintype "input"))
      (node (ref "C11") (pin "1") (pinfunction "1_1") (pintype "passive"))
      (node (ref "C12") (pin "1") (pinfunction "1_1") (pintype "passive"))
      (node (ref "C13") (pin "1") (pinfunction "1_1") (pintype "passive"))
      (node (ref "C4") (pin "2") (pinfunction "2_2") (pintype "passive"))
      (node (ref "C50") (pin "+") (pinfunction "+_+") (pintype "passive"))
      (node (ref "C8") (pin "1") (pinfunction "1_1") (pintype "passive"))
      (node (ref "C9") (pin "1") (pinfunction "1_1") (pintype "passive"))
      (node (ref "D1") (pin "2") (pinfunction "C2_2") (pintype "passive"))
      (node (ref "D11") (pin "2") (pinfunction "C2_2") (pintype "passive"))
      (node (ref "D12") (pin "2") (pinfunction "C2_2") (pintype "passive"))
      (node (ref "D2") (pin "2") (pinfunction "C2_2") (pintype "passive"))
      (node (ref "D7") (pin "2") (pinfunction "C2_2") (pintype "passive"))
      (node (ref "IC14") (pin "2") (pinfunction "OUT_2") (pintype "passive"))
      (node (ref "IC6") (pin "1") (pinfunction "VDD_1") (pintype "bidirectional"))
      (node (ref "L2") (pin "1") (pinfunction "1_1") (pintype "passive"))
      (node (ref "R32") (pin "2") (pinfunction "2_2") (pintype "passive"))
      (node (ref "SWDIO") (pin "5") (pinfunction "5_5") (pintype "passive"))
      (node (ref "U$1") (pin "P$100") (pinfunction "VDD5_P$100") (pintype "bidirectional"))
      (node (ref "U$1") (pin "P$11") (pinfunction "VDD6_P$11") (pintype "bidirectional"))
      (node (ref "U$1") (pin "P$19") (pinfunction "VDD1_P$19") (pintype "bidirectional"))
      (node (ref "U$1") (pin "P$28") (pinfunction "VDD2_P$28") (pintype "bidirectional"))
      (node (ref "U$1") (pin "P$50") (pinfunction "VDD3_P$50") (pintype "bidirectional"))
      (node (ref "U$1") (pin "P$6") (pinfunction "VBAT_P$6") (pintype "bidirectional"))
      (node (ref "U$1") (pin "P$75") (pinfunction "VDD4_P$75") (pintype "bidirectional"))
    )
    (net (code "2") (name "+5V") (class "Default")
      (node (ref "5V") (pin "TP") (pinfunction "TP_TP") (pintype "input"))
      (node (ref "C35") (pin "+") (pinfunction "+_+") (pintype "passive"))
      (node (ref "C36") (pin "2") (pinfunction "2_2") (pintype "passive"))
      (node (ref "C51") (pin "1") (pinfunction "1_1") (pintype "passive"))
      (node (ref "DISPLAY") (pin "3") (pinfunction "VCC_3") (pintype "bidirectional"))
      (node (ref "IC14") (pin "3") (pinfunction "IN_3") (pintype "input"))
      (node (ref "IC9") (pin "4") (pinfunction "/SHDN_4") (pintype "input"))
      (node (ref "IC9") (pin "5") (pinfunction "VIN_5") (pintype "power_in"))
      (node (ref "L3") (pin "2") (pinfunction "2_2") (pintype "passive"))
      (node (ref "L4") (pin "1") (pinfunction "1_1") (pintype "passive"))
      (node (ref "R52") (pin "2") (pinfunction "2_2") (pintype "passive"))
      (node (ref "R66") (pin "1") (pinfunction "1_1") (pintype "passive"))
    )
    (net (code "3") (name "+24V") (class "Default")
      (node (ref "C42") (pin "+") (pinfunction "+_+") (pintype "passive"))
      (node (ref "C43") (pin "1") (pinfunction "1_1") (pintype "passive"))
      (node (ref "C44") (pin "1") (pinfunction "1_1") (pintype "passive"))
      (node (ref "C45") (pin "1") (pinfunction "1_1") (pintype "passive"))
      (node (ref "D4") (pin "1") (pinfunction "C_1") (pintype "passive"))
      (node (ref "IC1") (pin "7") (pinfunction "V+_7") (pintype "power_in"))
      (node (ref "IC10") (pin "7") (pinfunction "V+_7") (pintype "power_in"))
      (node (ref "IC11") (pin "8") (pinfunction "V+_8") (pintype "power_in"))
      (node (ref "IC13") (pin "7") (pinfunction "V+_7") (pintype "power_in"))
      (node (ref "IC2") (pin "7") (pinfunction "V+_7") (pintype "power_in"))
      (node (ref "IC5") (pin "7") (pinfunction "V+_7") (pintype "power_in"))
      (node (ref "IC7") (pin "4") (pinfunction "V+_4") (pintype "power_in"))
      (node (ref "K1") (pin "1") (pinfunction "1_1") (pintype "passive"))
      (node (ref "L9") (pin "2") (pinfunction "2_2") (pintype "passive"))
      (node (ref "R26") (pin "2") (pinfunction "2_2") (pintype "passive"))
      (node (ref "R27") (pin "2") (pinfunction "2_2") (pintype "passive"))
    )
    (net (code "4") (name "-8V") (class "Default")
      (node (ref "-8V") (pin "TP") (pinfunction "TP_TP") (pintype "input"))
      (node (ref "C41") (pin "-") (pinfunction "-_-") (pintype "passive"))
      (node (ref "C43") (pin "2") (pinfunction "2_2") (pintype "passive"))
      (node (ref "C44") (pin "2") (pinfunction "2_2") (pintype "passive"))
      (node (ref "C45") (pin "2") (pinfunction "2_2") (pintype "passive"))
      (node (ref "IC1") (pin "4") (pinfunction "V-_4") (pintype "power_in"))
      (node (ref "IC10") (pin "4") (pinfunction "V-_4") (pintype "power_in"))
      (node (ref "IC11") (pin "4") (pinfunction "V-_4") (pintype "power_in"))
      (node (ref "IC13") (pin "4") (pinfunction "V-_4") (pintype "power_in"))
      (node (ref "IC2") (pin "4") (pinfunction "V-_4") (pintype "power_in"))
      (node (ref "IC5") (pin "4") (pinfunction "V-_4") (pintype "power_in"))
      (node (ref "IC7") (pin "11") (pinfunction "V-_11") (pintype "power_in"))
      (node (ref "L8") (pin "2") (pinfunction "2_2") (pintype "passive"))
    )
    (net (code "5") (name "2.5V") (class "Default")
      (node (ref "2V5") (pin "TP") (pinfunction "TP_TP") (pintype "input"))
      (node (ref "IC5") (pin "2") (pinfunction "-IN_2") (pintype "input"))
      (node (ref "IC5") (pin "6") (pinfunction "OUT_6") (pintype "output"))
      (node (ref "R14") (pin "2") (pinfunction "2_2") (pintype "passive"))
      (node (ref "R18") (pin "2") (pinfunction "2_2") (pintype "passive"))
      (node (ref "R51") (pin "2") (pinfunction "2_2") (pintype "passive"))
    )
    (net (code "6") (name "ADC_BATTERY") (class "Default")
      (node (ref "C48") (pin "1") (pinfunction "1_1") (pintype "passive"))
      (node (ref "D12") (pin "3") (pinfunction "C1A2_3") (pintype "passive"))
      (node (ref "R61") (pin "2") (pinfunction "2_2") (pintype "passive"))
      (node (ref "R62") (pin "1") (pinfunction "1_1") (pintype "passive"))
      (node (ref "U$1") (pin "P$18") (pinfunction "PC3/SPI2_MOSI_P$18") (pintype "bidirectional"))
    )
    (net (code "7") (name "ADC_BIAS_CURRENT") (class "Default")
      (node (ref "C23") (pin "1") (pinfunction "1_1") (pintype "passive"))
      (node (ref "D7") (pin "3") (pinfunction "C1A2_3") (pintype "passive"))
      (node (ref "R49") (pin "1") (pinfunction "1_1") (pintype "passive"))
      (node (ref "U$1") (pin "P$25") (pinfunction "PA2/USART2_TX_P$25") (pintype "bidirectional"))
    )
    (net (code "8") (name "ADC_HIGH_CURRENT") (class "Default")
      (node (ref "C2") (pin "1") (pinfunction "1_1") (pintype "passive"))
      (node (ref "D1") (pin "3") (pinfunction "C1A2_3") (pintype "passive"))
      (node (ref "R24") (pin "1") (pinfunction "1_1") (pintype "passive"))
      (node (ref "U$1") (pin "P$24") (pinfunction "PA1/UART4_RX_P$24") (pintype "bidirectional"))
    )
    (net (code "9") (name "ADC_LOW_CURRENT") (class "Default")
      (node (ref "C3") (pin "1") (pinfunction "1_1") (pintype "passive"))
      (node (ref "D2") (pin "3") (pinfunction "C1A2_3") (pintype "passive"))
      (node (ref "R25") (pin "1") (pinfunction "1_1") (pintype "passive"))
      (node (ref "U$1") (pin "P$26") (pinfunction "PA3/USART2_RX_P$26") (pintype "bidirectional"))
    )
    (net (code "10") (name "ADC_PUSHPULL_OUT") (class "Default")
      (node (ref "C47") (pin "1") (pinfunction "1_1") (pintype "passive"))
      (node (ref "D11") (pin "3") (pinfunction "C1A2_3") (pintype "passive"))
      (node (ref "R60") (pin "2") (pinfunction "2_2") (pintype "passive"))
      (node (ref "R67") (pin "1") (pinfunction "1_1") (pintype "passive"))
      (node (ref "U$1") (pin "P$23") (pinfunction "PA0/UART4_TX_P$23") (pintype "bidirectional"))
    )
    (net (code "11") (name "ADC_SUPPLY_HIGHSIDE") (class "Default")
      (node (ref "C46") (pin "1") (pinfunction "1_1") (pintype "passive"))
      (node (ref "R58") (pin "2") (pinfunction "2_2") (pintype "passive"))
      (node (ref "R59") (pin "1") (pinfunction "1_1") (pintype "passive"))
      (node (ref "U$1") (pin "P$17") (pinfunction "PC2/SPI2_MISO_P$17") (pintype "bidirectional"))
    )
    (net (code "12") (name "BATTERY+") (class "Default")
      (node (ref "+") (pin "1@1") (pinfunction "1_1@1") (pintype "bidirectional"))
      (node (ref "+") (pin "1@2") (pinfunction "2_1@2") (pintype "bidirectional"))
      (node (ref "C53") (pin "+") (pinfunction "+_+") (pintype "passive"))
      (node (ref "L6") (pin "2") (pinfunction "2_2") (pintype "passive"))
      (node (ref "R61") (pin "1") (pinfunction "1_1") (pintype "passive"))
    )
    (net (code "13") (name "BIAS_CTRL") (class "Default")
      (node (ref "IC6") (pin "6") (pinfunction "VB_6") (pintype "bidirectional"))
      (node (ref "R28") (pin "2") (pinfunction "2_2") (pintype "passive"))
    )
    (net (code "14") (name "BIAS_CURRENT") (class "Default")
      (node (ref "Q6") (pin "B") (pinfunction "B_B") (pintype "passive"))
      (node (ref "Q7") (pin "B") (pinfunction "B_B") (pintype "passive"))
      (node (ref "Q7") (pin "C") (pinfunction "C_C") (pintype "passive"))
      (node (ref "Q9") (pin "C") (pinfunction "C_C") (pintype "passive"))
    )
    (net (code "15") (name "BUCK_ENABLE") (class "Default")
      (node (ref "IC8") (pin "7") (pinfunction "ON_7") (pintype "passive"))
      (node (ref "R71") (pin "1") (pinfunction "1_1") (pintype "passive"))
    )
    (net (code "16") (name "CURRENT_CTRL") (class "Default")
      (node (ref "IC7") (pin "12") (pinfunction "+IN_12") (pintype "input"))
      (node (ref "R34") (pin "2") (pinfunction "2_2") (pintype "passive"))
      (node (ref "R70") (pin "2") (pinfunction "2_2") (pintype "passive"))
    )
    (net (code "17") (name "CURRENT_SENSE") (class "Default")
      (node (ref "C19") (pin "2") (pinfunction "2_2") (pintype "passive"))
      (node (ref "C20") (pin "2") (pinfunction "2_2") (pintype "passive"))
      (node (ref "IC13") (pin "6") (pinfunction "OUT_6") (pintype "output"))
      (node (ref "R12") (pin "1") (pinfunction "1_1") (pintype "passive"))
      (node (ref "R15") (pin "2") (pinfunction "2_2") (pintype "passive"))
      (node (ref "R19") (pin "2") (pinfunction "2_2") (pintype "passive"))
      (node (ref "R35") (pin "2") (pinfunction "2_2") (pintype "passive"))
      (node (ref "R36") (pin "2") (pinfunction "2_2") (pintype "passive"))
    )
    (net (code "18") (name "DAC_CS") (class "Default")
      (node (ref "IC6") (pin "2") (pinfunction "CS_2") (pintype "bidirectional"))
      (node (ref "U$1") (pin "P$45") (pinfunction "PE14_P$45") (pintype "bidirectional"))
    )
    (net (code "19") (name "DAC_LDAC") (class "Default")
      (node (ref "IC6") (pin "5") (pinfunction "LDAC_5") (pintype "bidirectional"))
      (node (ref "U$1") (pin "P$42") (pinfunction "PE11_P$42") (pintype "bidirectional"))
    )
    (net (code "20") (name "DAC_SCK") (class "Default")
      (node (ref "IC6") (pin "3") (pinfunction "SCK_3") (pintype "bidirectional"))
      (node (ref "U$1") (pin "P$44") (pinfunction "PE13_P$44") (pintype "bidirectional"))
    )
    (net (code "21") (name "DAC_SDI") (class "Default")
      (node (ref "IC6") (pin "4") (pinfunction "SDI_4") (pintype "bidirectional"))
      (node (ref "U$1") (pin "P$43") (pinfunction "PE12_P$43") (pintype "bidirectional"))
    )
    (net (code "22") (name "GND") (class "Default")
      (node (ref "-") (pin "1@1") (pinfunction "1_1@1") (pintype "bidirectional"))
      (node (ref "-") (pin "1@2") (pinfunction "2_1@2") (pintype "bidirectional"))
      (node (ref "C1") (pin "2") (pinfunction "2_2") (pintype "passive"))
      (node (ref "C10") (pin "2") (pinfunction "2_2") (pintype "passive"))
      (node (ref "C11") (pin "2") (pinfunction "2_2") (pintype "passive"))
      (node (ref "C12") (pin "2") (pinfunction "2_2") (pintype "passive"))
      (node (ref "C13") (pin "2") (pinfunction "2_2") (pintype "passive"))
      (node (ref "C14") (pin "2") (pinfunction "2_2") (pintype "passive"))
      (node (ref "C15") (pin "1") (pinfunction "1_1") (pintype "passive"))
      (node (ref "C16") (pin "1") (pinfunction "1_1") (pintype "passive"))
      (node (ref "C2") (pin "2") (pinfunction "2_2") (pintype "passive"))
      (node (ref "C22") (pin "2") (pinfunction "2_2") (pintype "passive"))
      (node (ref "C23") (pin "2") (pinfunction "2_2") (pintype "passive"))
      (node (ref "C24") (pin "-") (pinfunction "-_-") (pintype "passive"))
      (node (ref "C25") (pin "-") (pinfunction "-_-") (pintype "passive"))
      (node (ref "C26") (pin "-") (pinfunction "-_-") (pintype "passive"))
      (node (ref "C27") (pin "2") (pinfunction "2_2") (pintype "passive"))
      (node (ref "C28") (pin "1") (pinfunction "1_1") (pintype "passive"))
      (node (ref "C29") (pin "2") (pinfunction "2_2") (pintype "passive"))
      (node (ref "C3") (pin "2") (pinfunction "2_2") (pintype "passive"))
      (node (ref "C30") (pin "2") (pinfunction "2_2") (pintype "passive"))
      (node (ref "C31") (pin "2") (pinfunction "2_2") (pintype "passive"))
      (node (ref "C32") (pin "2") (pinfunction "2_2") (pintype "passive"))
      (node (ref "C34") (pin "1") (pinfunction "1_1") (pintype "passive"))
      (node (ref "C35") (pin "-") (pinfunction "-_-") (pintype "passive"))
      (node (ref "C36") (pin "1") (pinfunction "1_1") (pintype "passive"))
      (node (ref "C38") (pin "2") (pinfunction "2_2") (pintype "passive"))
      (node (ref "C4") (pin "1") (pinfunction "1_1") (pintype "passive"))
      (node (ref "C40") (pin "+") (pinfunction "+_+") (pintype "passive"))
      (node (ref "C41") (pin "+") (pinfunction "+_+") (pintype "passive"))
      (node (ref "C42") (pin "-") (pinfunction "-_-") (pintype "passive"))
      (node (ref "C46") (pin "2") (pinfunction "2_2") (pintype "passive"))
      (node (ref "C47") (pin "2") (pinfunction "2_2") (pintype "passive"))
      (node (ref "C48") (pin "2") (pinfunction "2_2") (pintype "passive"))
      (node (ref "C49") (pin "2") (pinfunction "2_2") (pintype "passive"))
      (node (ref "C50") (pin "-") (pinfunction "-_-") (pintype "passive"))
      (node (ref "C51") (pin "2") (pinfunction "2_2") (pintype "passive"))
      (node (ref "C52") (pin "1") (pinfunction "1_1") (pintype "passive"))
      (node (ref "C53") (pin "-") (pinfunction "-_-") (pintype "passive"))
      (node (ref "C54") (pin "2") (pinfunction "2_2") (pintype "passive"))
      (node (ref "C7") (pin "2") (pinfunction "2_2") (pintype "passive"))
      (node (ref "C8") (pin "2") (pinfunction "2_2") (pintype "passive"))
      (node (ref "C9") (pin "2") (pinfunction "2_2") (pintype "passive"))
      (node (ref "D1") (pin "1") (pinfunction "A1_1") (pintype "passive"))
      (node (ref "D10") (pin "A") (pinfunction "A_A") (pintype "passive"))
      (node (ref "D11") (pin "1") (pinfunction "A1_1") (pintype "passive"))
      (node (ref "D12") (pin "1") (pinfunction "A1_1") (pintype "passive"))
      (node (ref "D13") (pin "2") (pinfunction "COM_2") (pintype "bidirectional"))
      (node (ref "D2") (pin "1") (pinfunction "A1_1") (pintype "passive"))
      (node (ref "D6") (pin "A") (pinfunction "A_A") (pintype "passive"))
      (node (ref "D7") (pin "1") (pinfunction "A1_1") (pintype "passive"))
      (node (ref "D8") (pin "C") (pinfunction "C_C") (pintype "passive"))
      (node (ref "D9") (pin "1") (pinfunction "A1_1") (pintype "passive"))
      (node (ref "DISPLAY") (pin "1") (pinfunction "GND_1") (pintype "bidirectional"))
      (node (ref "IC11") (pin "3") (pinfunction "+IN_3") (pintype "input"))
      (node (ref "IC11") (pin "5") (pinfunction "+IN_5") (pintype "input"))
      (node (ref "IC12") (pin "3") (pinfunction "INH_3") (pintype "input"))
      (node (ref "IC12") (pin "7") (pinfunction "GND_7") (pintype "power_in"))
      (node (ref "IC12") (pin "EXP") (pinfunction "EXP_EXP") (pintype "input"))
      (node (ref "IC14") (pin "1") (pinfunction "GND_1") (pintype "input"))
      (node (ref "IC4") (pin "2") (pinfunction "A_2") (pintype "passive"))
      (node (ref "IC4") (pin "3") (pinfunction "A_3") (pintype "passive"))
      (node (ref "IC4") (pin "6") (pinfunction "A_6") (pintype "passive"))
      (node (ref "IC4") (pin "7") (pinfunction "A_7") (pintype "passive"))
      (node (ref "IC6") (pin "7") (pinfunction "VSS_7") (pintype "bidirectional"))
      (node (ref "IC7") (pin "5") (pinfunction "+IN_5") (pintype "input"))
      (node (ref "IC8") (pin "4") (pinfunction "GND_4") (pintype "power_in"))
      (node (ref "IC9") (pin "2") (pinfunction "GND_2") (pintype "power_in"))
      (node (ref "LED1") (pin "C") (pinfunction "C_C") (pintype "passive"))
      (node (ref "LED2") (pin "C") (pinfunction "C_C") (pintype "passive"))
      (node (ref "PAD2") (pin "1") (pinfunction "P_1") (pintype "passive"))
      (node (ref "Q11") (pin "E") (pinfunction "E_E") (pintype "passive"))
      (node (ref "Q12") (pin "E") (pinfunction "E_E") (pintype "passive"))
      (node (ref "Q13") (pin "E") (pinfunction "E_E") (pintype "passive"))
      (node (ref "Q15") (pin "2") (pinfunction "S_2") (pintype "passive"))
      (node (ref "R13") (pin "1") (pinfunction "1_1") (pintype "passive"))
      (node (ref "R17") (pin "2") (pinfunction "2_2") (pintype "passive"))
      (node (ref "R21") (pin "2") (pinfunction "2_2") (pintype "passive"))
      (node (ref "R44") (pin "1") (pinfunction "1_1") (pintype "passive"))
      (node (ref "R45") (pin "1") (pinfunction "1_1") (pintype "passive"))
      (node (ref "R47") (pin "2") (pinfunction "2_2") (pintype "passive"))
      (node (ref "R48") (pin "1") (pinfunction "1_1") (pintype "passive"))
      (node (ref "R50") (pin "1") (pinfunction "1_1") (pintype "passive"))
      (node (ref "R53") (pin "1") (pinfunction "1_1") (pintype "passive"))
      (node (ref "R54") (pin "1") (pinfunction "1_1") (pintype "passive"))
      (node (ref "R55") (pin "1") (pinfunction "1_1") (pintype "passive"))
      (node (ref "R59") (pin "2") (pinfunction "2_2") (pintype "passive"))
      (node (ref "R62") (pin "2") (pinfunction "2_2") (pintype "passive"))
      (node (ref "R67") (pin "2") (pinfunction "2_2") (pintype "passive"))
      (node (ref "S1") (pin "2") (pinfunction "S_2") (pintype "passive"))
      (node (ref "SWDIO") (pin "3") (pinfunction "3_3") (pintype "passive"))
      (node (ref "U$1") (pin "P$10") (pinfunction "VSS1_P$10") (pintype "bidirectional"))
      (node (ref "U$1") (pin "P$20") (pinfunction "VSSA_P$20") (pintype "bidirectional"))
      (node (ref "U$1") (pin "P$27") (pinfunction "VSS2_P$27") (pintype "bidirectional"))
      (node (ref "U$1") (pin "P$74") (pinfunction "VSS3_P$74") (pintype "bidirectional"))
      (node (ref "U$1") (pin "P$94") (pinfunction "BOOT0_P$94") (pintype "bidirectional"))
      (node (ref "U$1") (pin "P$99") (pinfunction "VSS4_P$99") (pintype "bidirectional"))
      (node (ref "UART") (pin "1") (pinfunction "1_1") (pintype "passive"))
      (node (ref "X1") (pin "5") (pinfunction "5_5") (pintype "passive"))
      (node (ref "X1") (pin "M1") (pinfunction "S1_M1") (pintype "passive"))
      (node (ref "X1") (pin "M2") (pinfunction "S2_M2") (pintype "passive"))
      (node (ref "X1") (pin "M3") (pinfunction "S3_M3") (pintype "passive"))
      (node (ref "X1") (pin "M4") (pinfunction "S4_M4") (pintype "passive"))
    )
    (net (code "23") (name "HIGHSIDE_SUPPLY_CTRL") (class "Default")
      (node (ref "IC6") (pin "8") (pinfunction "VA_8") (pintype "bidirectional"))
      (node (ref "R43") (pin "1") (pinfunction "1_1") (pintype "passive"))
    )
    (net (code "24") (name "LCD_CLK") (class "Default")
      (node (ref "DISPLAY") (pin "18") (pinfunction "CLK_18") (pintype "bidirectional"))
      (node (ref "DISPLAY") (pin "32") (pinfunction "CLK_32") (pintype "bidirectional"))
      (node (ref "U$1") (pin "P$78") (pinfunction "PC10/SPI3_SCK/USART3_TX/UART4_TX_P$78") (pintype "bidirectional"))
    )
    (net (code "25") (name "LCD_CS") (class "Default")
      (node (ref "DISPLAY") (pin "29") (pinfunction "CS_29") (pintype "bidirectional"))
      (node (ref "U$1") (pin "P$95") (pinfunction "PB8/I2C1_SCL/CAN1_RX_P$95") (pintype "bidirectional"))
    )
    (net (code "26") (name "LCD_MISO") (class "Default")
      (node (ref "DISPLAY") (pin "26") (pinfunction "DOUT_26") (pintype "bidirectional"))
      (node (ref "DISPLAY") (pin "30") (pinfunction "MISO_30") (pintype "bidirectional"))
      (node (ref "U$1") (pin "P$79") (pinfunction "PC11/SPI3_MISO/USART3_RX/UART4_RX_P$79") (pintype "bidirectional"))
    )
    (net (code "27") (name "LCD_MOSI") (class "Default")
      (node (ref "DISPLAY") (pin "22") (pinfunction "DIN_22") (pintype "bidirectional"))
      (node (ref "DISPLAY") (pin "34") (pinfunction "MOSI_34") (pintype "bidirectional"))
      (node (ref "U$1") (pin "P$80") (pinfunction "PC12/SPI3_MOSI/UART5_TX_P$80") (pintype "bidirectional"))
    )
    (net (code "28") (name "LCD_RD") (class "Default")
      (node (ref "DISPLAY") (pin "11") (pinfunction "RD_11") (pintype "bidirectional"))
      (node (ref "U$1") (pin "P$66") (pinfunction "PC9/I2C3_SDA_P$66") (pintype "bidirectional"))
    )
    (net (code "29") (name "LCD_RESET") (class "Default")
      (node (ref "DISPLAY") (pin "33") (pinfunction "RST_33") (pintype "bidirectional"))
      (node (ref "U$1") (pin "P$96") (pinfunction "PB9/I2C1_SDA/CAN1_TX_P$96") (pintype "bidirectional"))
    )
    (net (code "30") (name "LCD_RS") (class "Default")
      (node (ref "DISPLAY") (pin "7") (pinfunction "RS_7") (pintype "bidirectional"))
      (node (ref "U$1") (pin "P$64") (pinfunction "PC7/USART6_RX_P$64") (pintype "bidirectional"))
    )
    (net (code "31") (name "LCD_SD_CS") (class "Default")
      (node (ref "DISPLAY") (pin "36") (pinfunction "CS_36") (pintype "bidirectional"))
      (node (ref "U$1") (pin "P$97") (pinfunction "PE0_P$97") (pintype "bidirectional"))
    )
    (net (code "32") (name "LCD_TOUCH_BUSY") (class "Default")
      (node (ref "DISPLAY") (pin "24") (pinfunction "BUSY_24") (pintype "bidirectional"))
      (node (ref "U$1") (pin "P$90") (pinfunction "PB4/SPI1_MISO/SPI3_MISO_P$90") (pintype "bidirectional"))
    )
    (net (code "33") (name "LCD_TOUCH_CS") (class "Default")
      (node (ref "DISPLAY") (pin "20") (pinfunction "CS_20") (pintype "bidirectional"))
      (node (ref "U$1") (pin "P$89") (pinfunction "PB3/SPI1_SCK/SPI3_SCK_P$89") (pintype "bidirectional"))
    )
    (net (code "34") (name "LCD_TOUCH_IRQ") (class "Default")
      (node (ref "DISPLAY") (pin "28") (pinfunction "IRQ_28") (pintype "bidirectional"))
      (node (ref "U$1") (pin "P$91") (pinfunction "PB5/SPI1_MOSI/SPI3_MOSI/CAN2_RX_P$91") (pintype "bidirectional"))
    )
    (net (code "35") (name "LCD_WR") (class "Default")
      (node (ref "DISPLAY") (pin "9") (pinfunction "WR_9") (pintype "bidirectional"))
      (node (ref "U$1") (pin "P$65") (pinfunction "PC8_P$65") (pintype "bidirectional"))
    )
    (net (code "36") (name "LED1") (class "Default")
      (node (ref "R63") (pin "1") (pinfunction "1_1") (pintype "passive"))
      (node (ref "U$1") (pin "P$2") (pinfunction "PE3_P$2") (pintype "bidirectional"))
    )
    (net (code "37") (name "LED2") (class "Default")
      (node (ref "R65") (pin "1") (pinfunction "1_1") (pintype "passive"))
      (node (ref "U$1") (pin "P$3") (pinfunction "PE4_P$3") (pintype "bidirectional"))
    )
    (net (code "38") (name "NRST") (class "Default")
      (node (ref "C14") (pin "1") (pinfunction "1_1") (pintype "passive"))
      (node (ref "R32") (pin "1") (pinfunction "1_1") (pintype "passive"))
      (node (ref "SWDIO") (pin "1") (pinfunction "1_1") (pintype "passive"))
      (node (ref "U$1") (pin "P$14") (pinfunction "NRST_P$14") (pintype "bidirectional"))
    )
    (net (code "39") (name "Net-(C33-Pad2)") (class "Default")
      (node (ref "C33") (pin "2") (pinfunction "2_2") (pintype "passive"))
      (node (ref "R54") (pin "2") (pinfunction "2_2") (pintype "passive"))
    )
    (net (code "40") (name "Net-(C37-Pad1)") (class "Default")
      (node (ref "C37") (pin "1") (pinfunction "1_1") (pintype "passive"))
      (node (ref "D8") (pin "A") (pinfunction "A_A") (pintype "passive"))
      (node (ref "L5") (pin "1") (pinfunction "1_1") (pintype "passive"))
    )
    (net (code "41") (name "Net-(C38-Pad1)") (class "Default")
      (node (ref "C38") (pin "1") (pinfunction "1_1") (pintype "passive"))
      (node (ref "R55") (pin "2") (pinfunction "2_2") (pintype "passive"))
      (node (ref "R56") (pin "1") (pinfunction "1_1") (pintype "passive"))
    )
    (net (code "42") (name "Net-(C39-Pad1)") (class "Default")
      (node (ref "C39") (pin "1") (pinfunction "1_1") (pintype "passive"))
      (node (ref "C40") (pin "-") (pinfunction "-_-") (pintype "passive"))
      (node (ref "L5") (pin "2") (pinfunction "2_2") (pintype "passive"))
      (node (ref "L8") (pin "1") (pinfunction "1_1") (pintype "passive"))
      (node (ref "R57") (pin "2") (pinfunction "2_2") (pintype "passive"))
    )
    (net (code "43") (name "Net-(C52-Pad2)") (class "Default")
      (node (ref "C52") (pin "2") (pinfunction "2_2") (pintype "passive"))
      (node (ref "R37") (pin "1") (pinfunction "1_1") (pintype "passive"))
      (node (ref "R68") (pin "2") (pinfunction "2_2") (pintype "passive"))
    )
    (net (code "44") (name "Net-(D3-A)") (class "Default")
      (node (ref "D3") (pin "2") (pinfunction "A_2") (pintype "passive"))
      (node (ref "D5") (pin "2") (pinfunction "A_2") (pintype "passive"))
      (node (ref "Q5") (pin "B") (pinfunction "B_B") (pintype "passive"))
      (node (ref "Q8") (pin "B") (pinfunction "B_B") (pintype "passive"))
      (node (ref "Q8") (pin "C") (pinfunction "C_C") (pintype "passive"))
    )
    (net (code "45") (name "Net-(D3-C)") (class "Default")
      (node (ref "D3") (pin "1") (pinfunction "C_1") (pintype "passive"))
      (node (ref "Q14") (pin "E") (pinfunction "E_E") (pintype "passive"))
    )
    (net (code "46") (name "Net-(D4-A)") (class "Default")
      (node (ref "D4") (pin "2") (pinfunction "A_2") (pintype "passive"))
      (node (ref "K1") (pin "2") (pinfunction "2_2") (pintype "passive"))
      (node (ref "Q13") (pin "C") (pinfunction "C_C") (pintype "passive"))
    )
    (net (code "47") (name "Net-(D5-C)") (class "Default")
      (node (ref "C18") (pin "2") (pinfunction "2_2") (pintype "passive"))
      (node (ref "D5") (pin "1") (pinfunction "C_1") (pintype "passive"))
      (node (ref "IC7") (pin "14") (pinfunction "OUT_14") (pintype "output"))
    )
    (net (code "48") (name "Net-(D9-C1A2)") (class "Default")
      (node (ref "D9") (pin "3") (pinfunction "C1A2_3") (pintype "passive"))
      (node (ref "IC8") (pin "6") (pinfunction "FB_6") (pintype "input"))
      (node (ref "R37") (pin "2") (pinfunction "2_2") (pintype "passive"))
      (node (ref "R38") (pin "1") (pinfunction "1_1") (pintype "passive"))
    )
    (net (code "49") (name "Net-(D13-2)") (class "Default")
      (node (ref "D13") (pin "3") (pinfunction "2_3") (pintype "bidirectional"))
      (node (ref "R97") (pin "1") (pinfunction "1_1") (pintype "passive"))
      (node (ref "X1") (pin "3") (pinfunction "3_3") (pintype "passive"))
    )
    (net (code "50") (name "Net-(D13-3)") (class "Default")
      (node (ref "D13") (pin "4") (pinfunction "3_4") (pintype "bidirectional"))
      (node (ref "R98") (pin "1") (pinfunction "1_1") (pintype "passive"))
      (node (ref "X1") (pin "1") (pinfunction "1_1") (pintype "passive"))
    )
    (net (code "51") (name "Net-(D13-4)") (class "Default")
      (node (ref "D13") (pin "5") (pinfunction "4_5") (pintype "bidirectional"))
      (node (ref "R64") (pin "1") (pinfunction "1_1") (pintype "passive"))
      (node (ref "X1") (pin "2") (pinfunction "2_2") (pintype "passive"))
    )
    (net (code "52") (name "Net-(D13-Pad1)") (class "Default")
      (node (ref "D13") (pin "1") (pinfunction "1_1") (pintype "bidirectional"))
      (node (ref "R100") (pin "1") (pinfunction "1_1") (pintype "passive"))
      (node (ref "X1") (pin "4") (pinfunction "4_4") (pintype "passive"))
    )
    (net (code "53") (name "Net-(DISPLAYC-DB0)") (class "Default")
      (node (ref "DISPLAY") (pin "2") (pinfunction "DB0_2") (pintype "bidirectional"))
      (node (ref "U$1") (pin "P$55") (pinfunction "PD8/USART3_TX_P$55") (pintype "bidirectional"))
    )
    (net (code "54") (name "Net-(DISPLAYC-DB1)") (class "Default")
      (node (ref "DISPLAY") (pin "4") (pinfunction "DB1_4") (pintype "bidirectional"))
      (node (ref "U$1") (pin "P$56") (pinfunction "PD9/USART3_RX_P$56") (pintype "bidirectional"))
    )
    (net (code "55") (name "Net-(DISPLAYC-DB2)") (class "Default")
      (node (ref "DISPLAY") (pin "6") (pinfunction "DB2_6") (pintype "bidirectional"))
      (node (ref "U$1") (pin "P$57") (pinfunction "PD10_P$57") (pintype "bidirectional"))
    )
    (net (code "56") (name "Net-(DISPLAYC-DB3)") (class "Default")
      (node (ref "DISPLAY") (pin "8") (pinfunction "DB3_8") (pintype "bidirectional"))
      (node (ref "U$1") (pin "P$58") (pinfunction "PD11_P$58") (pintype "bidirectional"))
    )
    (net (code "57") (name "Net-(DISPLAYC-DB4)") (class "Default")
      (node (ref "DISPLAY") (pin "10") (pinfunction "DB4_10") (pintype "bidirectional"))
      (node (ref "U$1") (pin "P$59") (pinfunction "PD12_P$59") (pintype "bidirectional"))
    )
    (net (code "58") (name "Net-(DISPLAYC-DB5)") (class "Default")
      (node (ref "DISPLAY") (pin "12") (pinfunction "DB5_12") (pintype "bidirectional"))
      (node (ref "U$1") (pin "P$60") (pinfunction "PD13_P$60") (pintype "bidirectional"))
    )
    (net (code "59") (name "Net-(DISPLAYC-DB6)") (class "Default")
      (node (ref "DISPLAY") (pin "14") (pinfunction "DB6_14") (pintype "bidirectional"))
      (node (ref "U$1") (pin "P$61") (pinfunction "PD14_P$61") (pintype "bidirectional"))
    )
    (net (code "60") (name "Net-(DISPLAYC-DB7)") (class "Default")
      (node (ref "DISPLAY") (pin "16") (pinfunction "DB7_16") (pintype "bidirectional"))
      (node (ref "U$1") (pin "P$62") (pinfunction "PD15_P$62") (pintype "bidirectional"))
    )
    (net (code "61") (name "Net-(DISPLAYC-DB8)") (class "Default")
      (node (ref "DISPLAY") (pin "13") (pinfunction "DB8_13") (pintype "bidirectional"))
      (node (ref "U$1") (pin "P$81") (pinfunction "PD0/CAN1_RX_P$81") (pintype "bidirectional"))
    )
    (net (code "62") (name "Net-(DISPLAYC-DB9)") (class "Default")
      (node (ref "DISPLAY") (pin "15") (pinfunction "DB9_15") (pintype "bidirectional"))
      (node (ref "U$1") (pin "P$82") (pinfunction "PD1/CAN1_TX_P$82") (pintype "bidirectional"))
    )
    (net (code "63") (name "Net-(DISPLAYC-DB10)") (class "Default")
      (node (ref "DISPLAY") (pin "17") (pinfunction "DB10_17") (pintype "bidirectional"))
      (node (ref "U$1") (pin "P$83") (pinfunction "PD2/UART5_RX_P$83") (pintype "bidirectional"))
    )
    (net (code "64") (name "Net-(DISPLAYC-DB11)") (class "Default")
      (node (ref "DISPLAY") (pin "19") (pinfunction "DB11_19") (pintype "bidirectional"))
      (node (ref "U$1") (pin "P$84") (pinfunction "PD3_P$84") (pintype "bidirectional"))
    )
    (net (code "65") (name "Net-(DISPLAYC-DB12)") (class "Default")
      (node (ref "DISPLAY") (pin "21") (pinfunction "DB12_21") (pintype "bidirectional"))
      (node (ref "U$1") (pin "P$85") (pinfunction "PD4_P$85") (pintype "bidirectional"))
    )
    (net (code "66") (name "Net-(DISPLAYC-DB13)") (class "Default")
      (node (ref "DISPLAY") (pin "23") (pinfunction "DB13_23") (pintype "bidirectional"))
      (node (ref "U$1") (pin "P$86") (pinfunction "PD5/USART2_TX_P$86") (pintype "bidirectional"))
    )
    (net (code "67") (name "Net-(DISPLAYC-DB14)") (class "Default")
      (node (ref "DISPLAY") (pin "25") (pinfunction "DB14_25") (pintype "bidirectional"))
      (node (ref "U$1") (pin "P$87") (pinfunction "PD6/USART2_RX_P$87") (pintype "bidirectional"))
    )
    (net (code "68") (name "Net-(DISPLAYC-DB15)") (class "Default")
      (node (ref "DISPLAY") (pin "27") (pinfunction "DB15_27") (pintype "bidirectional"))
      (node (ref "U$1") (pin "P$88") (pinfunction "PD7_P$88") (pintype "bidirectional"))
    )
    (net (code "69") (name "Net-(DISPLAYD-LED_A+)") (class "Default")
      (node (ref "DISPLAY") (pin "37") (pinfunction "LED_A+_37") (pintype "bidirectional"))
      (node (ref "R66") (pin "2") (pinfunction "2_2") (pintype "passive"))
    )
    (net (code "70") (name "Net-(IC1-+IN)") (class "Default")
      (node (ref "IC1") (pin "3") (pinfunction "+IN_3") (pintype "input"))
      (node (ref "R18") (pin "1") (pinfunction "1_1") (pintype "passive"))
      (node (ref "R21") (pin "1") (pinfunction "1_1") (pintype "passive"))
    )
    (net (code "71") (name "Net-(IC1--IN)") (class "Default")
      (node (ref "IC1") (pin "2") (pinfunction "-IN_2") (pintype "input"))
      (node (ref "R19") (pin "1") (pinfunction "1_1") (pintype "passive"))
      (node (ref "R20") (pin "2") (pinfunction "2_2") (pintype "passive"))
    )
    (net (code "72") (name "Net-(IC1-OUT)") (class "Default")
      (node (ref "IC1") (pin "6") (pinfunction "OUT_6") (pintype "output"))
      (node (ref "R20") (pin "1") (pinfunction "1_1") (pintype "passive"))
      (node (ref "R25") (pin "2") (pinfunction "2_2") (pintype "passive"))
    )
    (net (code "73") (name "Net-(IC2-+IN)") (class "Default")
      (node (ref "IC2") (pin "3") (pinfunction "+IN_3") (pintype "input"))
      (node (ref "R14") (pin "1") (pinfunction "1_1") (pintype "passive"))
      (node (ref "R17") (pin "1") (pinfunction "1_1") (pintype "passive"))
    )
    (net (code "74") (name "Net-(IC2--IN)") (class "Default")
      (node (ref "IC2") (pin "2") (pinfunction "-IN_2") (pintype "input"))
      (node (ref "R15") (pin "1") (pinfunction "1_1") (pintype "passive"))
      (node (ref "R16") (pin "2") (pinfunction "2_2") (pintype "passive"))
    )
    (net (code "75") (name "Net-(IC2-OUT)") (class "Default")
      (node (ref "IC2") (pin "6") (pinfunction "OUT_6") (pintype "output"))
      (node (ref "R16") (pin "1") (pinfunction "1_1") (pintype "passive"))
      (node (ref "R24") (pin "2") (pinfunction "2_2") (pintype "passive"))
    )
    (net (code "76") (name "Net-(IC4-C)") (class "Default")
      (node (ref "C54") (pin "1") (pinfunction "1_1") (pintype "passive"))
      (node (ref "IC4") (pin "1") (pinfunction "C_1") (pintype "passive"))
      (node (ref "IC4") (pin "8") (pinfunction "R_8") (pintype "passive"))
      (node (ref "R22") (pin "2") (pinfunction "2_2") (pintype "passive"))
      (node (ref "R23") (pin "1") (pinfunction "1_1") (pintype "passive"))
    )
    (net (code "77") (name "Net-(IC5-+IN)") (class "Default")
      (node (ref "C1") (pin "1") (pinfunction "1_1") (pintype "passive"))
      (node (ref "IC5") (pin "3") (pinfunction "+IN_3") (pintype "input"))
      (node (ref "R23") (pin "2") (pinfunction "2_2") (pintype "passive"))
    )
    (net (code "78") (name "Net-(IC7A-+IN)") (class "Default")
      (node (ref "IC7") (pin "3") (pinfunction "+IN_3") (pintype "input"))
      (node (ref "IC7") (pin "7") (pinfunction "OUT_7") (pintype "output"))
      (node (ref "R33") (pin "1") (pinfunction "1_1") (pintype "passive"))
    )
    (net (code "79") (name "Net-(IC7A--IN)") (class "Default")
      (node (ref "C17") (pin "1") (pinfunction "1_1") (pintype "passive"))
      (node (ref "C20") (pin "1") (pinfunction "1_1") (pintype "passive"))
      (node (ref "IC7") (pin "2") (pinfunction "-IN_2") (pintype "input"))
      (node (ref "R36") (pin "1") (pinfunction "1_1") (pintype "passive"))
      (node (ref "R50") (pin "2") (pinfunction "2_2") (pintype "passive"))
    )
    (net (code "80") (name "Net-(IC7A-OUT)") (class "Default")
      (node (ref "C17") (pin "2") (pinfunction "2_2") (pintype "passive"))
      (node (ref "IC7") (pin "1") (pinfunction "OUT_1") (pintype "output"))
      (node (ref "Q14") (pin "C") (pinfunction "C_C") (pintype "passive"))
    )
    (net (code "81") (name "Net-(IC7B--IN)") (class "Default")
      (node (ref "IC7") (pin "6") (pinfunction "-IN_6") (pintype "input"))
      (node (ref "R33") (pin "2") (pinfunction "2_2") (pintype "passive"))
      (node (ref "R34") (pin "1") (pinfunction "1_1") (pintype "passive"))
    )
    (net (code "82") (name "Net-(IC7C--IN)") (class "Default")
      (node (ref "C5") (pin "1") (pinfunction "1_1") (pintype "passive"))
      (node (ref "C6") (pin "1") (pinfunction "1_1") (pintype "passive"))
      (node (ref "IC7") (pin "9") (pinfunction "-IN_9") (pintype "input"))
      (node (ref "R29") (pin "1") (pinfunction "1_1") (pintype "passive"))
      (node (ref "R30") (pin "2") (pinfunction "2_2") (pintype "passive"))
      (node (ref "R44") (pin "2") (pinfunction "2_2") (pintype "passive"))
    )
    (net (code "83") (name "Net-(IC7C-OUT)") (class "Default")
      (node (ref "C5") (pin "2") (pinfunction "2_2") (pintype "passive"))
      (node (ref "IC7") (pin "8") (pinfunction "OUT_8") (pintype "output"))
      (node (ref "Q14") (pin "B") (pinfunction "B_B") (pintype "passive"))
    )
    (net (code "84") (name "Net-(IC7D--IN)") (class "Default")
      (node (ref "C18") (pin "1") (pinfunction "1_1") (pintype "passive"))
      (node (ref "C19") (pin "1") (pinfunction "1_1") (pintype "passive"))
      (node (ref "IC7") (pin "13") (pinfunction "-IN_13") (pintype "input"))
      (node (ref "R35") (pin "1") (pinfunction "1_1") (pintype "passive"))
      (node (ref "R48") (pin "2") (pinfunction "2_2") (pintype "passive"))
    )
    (net (code "85") (name "Net-(IC8-CB)") (class "Default")
      (node (ref "C21") (pin "1") (pinfunction "1_1") (pintype "passive"))
      (node (ref "IC8") (pin "3") (pinfunction "CB_3") (pintype "input"))
    )
    (net (code "86") (name "Net-(IC8-VSW)") (class "Default")
      (node (ref "C21") (pin "2") (pinfunction "2_2") (pintype "passive"))
      (node (ref "D6") (pin "C") (pinfunction "C_C") (pintype "passive"))
      (node (ref "IC8") (pin "1") (pinfunction "VSW_1") (pintype "output"))
      (node (ref "L1") (pin "1") (pinfunction "1_1") (pintype "passive"))
    )
    (net (code "87") (name "Net-(IC9-NFB)") (class "Default")
      (node (ref "C39") (pin "2") (pinfunction "2_2") (pintype "passive"))
      (node (ref "IC9") (pin "3") (pinfunction "NFB_3") (pintype "input"))
      (node (ref "R56") (pin "2") (pinfunction "2_2") (pintype "passive"))
      (node (ref "R57") (pin "1") (pinfunction "1_1") (pintype "passive"))
    )
    (net (code "88") (name "Net-(IC9-SW)") (class "Default")
      (node (ref "C37") (pin "2") (pinfunction "2_2") (pintype "passive"))
      (node (ref "IC9") (pin "1") (pinfunction "SW_1") (pintype "output"))
      (node (ref "L4") (pin "2") (pinfunction "2_2") (pintype "passive"))
    )
    (net (code "89") (name "Net-(IC10--IN)") (class "Default")
      (node (ref "IC10") (pin "2") (pinfunction "-IN_2") (pintype "input"))
      (node (ref "R46") (pin "2") (pinfunction "2_2") (pintype "passive"))
      (node (ref "R47") (pin "1") (pinfunction "1_1") (pintype "passive"))
    )
    (net (code "90") (name "Net-(IC10-OUT)") (class "Default")
      (node (ref "IC10") (pin "6") (pinfunction "OUT_6") (pintype "output"))
      (node (ref "R46") (pin "1") (pinfunction "1_1") (pintype "passive"))
      (node (ref "R49") (pin "2") (pinfunction "2_2") (pintype "passive"))
    )
    (net (code "91") (name "Net-(IC11A--IN)") (class "Default")
      (node (ref "IC11") (pin "2") (pinfunction "-IN_2") (pintype "input"))
      (node (ref "R42") (pin "1") (pinfunction "1_1") (pintype "passive"))
      (node (ref "R43") (pin "2") (pinfunction "2_2") (pintype "passive"))
    )
    (net (code "92") (name "Net-(IC11A-OUT)") (class "Default")
      (node (ref "IC11") (pin "1") (pinfunction "OUT_1") (pintype "output"))
      (node (ref "R41") (pin "1") (pinfunction "1_1") (pintype "passive"))
      (node (ref "R42") (pin "2") (pinfunction "2_2") (pintype "passive"))
    )
    (net (code "93") (name "Net-(IC11B--IN)") (class "Default")
      (node (ref "IC11") (pin "6") (pinfunction "-IN_6") (pintype "input"))
      (node (ref "R39") (pin "1") (pinfunction "1_1") (pintype "passive"))
      (node (ref "R40") (pin "2") (pinfunction "2_2") (pintype "passive"))
      (node (ref "R41") (pin "2") (pinfunction "2_2") (pintype "passive"))
    )
    (net (code "94") (name "Net-(IC11B-OUT)") (class "Default")
      (node (ref "IC11") (pin "7") (pinfunction "OUT_7") (pintype "output"))
      (node (ref "R39") (pin "2") (pinfunction "2_2") (pintype "passive"))
      (node (ref "R68") (pin "1") (pinfunction "1_1") (pintype "passive"))
    )
    (net (code "95") (name "Net-(IC12B-COMP)") (class "Default")
      (node (ref "C32") (pin "1") (pinfunction "1_1") (pintype "passive"))
      (node (ref "C33") (pin "1") (pinfunction "1_1") (pintype "passive"))
      (node (ref "IC12") (pin "4") (pinfunction "COMP_4") (pintype "passive"))
    )
    (net (code "96") (name "Net-(IC12B-FB)") (class "Default")
      (node (ref "IC12") (pin "5") (pinfunction "FB_5") (pintype "input"))
      (node (ref "R52") (pin "1") (pinfunction "1_1") (pintype "passive"))
      (node (ref "R53") (pin "2") (pinfunction "2_2") (pintype "passive"))
    )
    (net (code "97") (name "Net-(IC12B-OUT)") (class "Default")
      (node (ref "D10") (pin "C") (pinfunction "C_C") (pintype "passive"))
      (node (ref "IC12") (pin "1") (pinfunction "OUT_1") (pintype "output"))
      (node (ref "L3") (pin "1") (pinfunction "1_1") (pintype "passive"))
    )
    (net (code "98") (name "Net-(IC13A-IN+)") (class "Default")
      (node (ref "IC13") (pin "3") (pinfunction "IN+_3") (pintype "input"))
      (node (ref "R10") (pin "1") (pinfunction "1_1") (pintype "passive"))
      (node (ref "R13") (pin "2") (pinfunction "2_2") (pintype "passive"))
    )
    (net (code "99") (name "Net-(IC13A-IN-)") (class "Default")
      (node (ref "IC13") (pin "2") (pinfunction "IN-_2") (pintype "input"))
      (node (ref "R11") (pin "1") (pinfunction "1_1") (pintype "passive"))
      (node (ref "R12") (pin "2") (pinfunction "2_2") (pintype "passive"))
    )
    (net (code "100") (name "Net-(K1-PadS)") (class "Default")
      (node (ref "K1") (pin "S") (pinfunction "S_S") (pintype "passive"))
      (node (ref "L6") (pin "1") (pinfunction "1_1") (pintype "passive"))
    )
    (net (code "101") (name "Net-(LED1-PadA)") (class "Default")
      (node (ref "LED1") (pin "A") (pinfunction "A_A") (pintype "passive"))
      (node (ref "R63") (pin "2") (pinfunction "2_2") (pintype "passive"))
    )
    (net (code "102") (name "Net-(LED2-PadA)") (class "Default")
      (node (ref "LED2") (pin "A") (pinfunction "A_A") (pintype "passive"))
      (node (ref "R65") (pin "2") (pinfunction "2_2") (pintype "passive"))
    )
    (net (code "103") (name "Net-(Q1-PadB)") (class "Default")
      (node (ref "Q1") (pin "B") (pinfunction "B_B") (pintype "passive"))
      (node (ref "Q3") (pin "C") (pinfunction "C_C") (pintype "passive"))
      (node (ref "R5") (pin "1") (pinfunction "1_1") (pintype "passive"))
    )
    (net (code "104") (name "Net-(Q1-PadE)") (class "Default")
      (node (ref "Q1") (pin "E") (pinfunction "E_E") (pintype "passive"))
      (node (ref "Q5") (pin "E") (pinfunction "E_E") (pintype "passive"))
      (node (ref "R4") (pin "1") (pinfunction "1_1") (pintype "passive"))
      (node (ref "R5") (pin "2") (pinfunction "2_2") (pintype "passive"))
    )
    (net (code "105") (name "Net-(Q2-PadB)") (class "Default")
      (node (ref "Q2") (pin "B") (pinfunction "B_B") (pintype "passive"))
      (node (ref "Q4") (pin "C") (pinfunction "C_C") (pintype "passive"))
      (node (ref "R1") (pin "2") (pinfunction "2_2") (pintype "passive"))
    )
    (net (code "106") (name "Net-(Q3-PadB)") (class "Default")
      (node (ref "Q3") (pin "B") (pinfunction "B_B") (pintype "passive"))
      (node (ref "Q5") (pin "C") (pinfunction "C_C") (pintype "passive"))
      (node (ref "R6") (pin "1") (pinfunction "1_1") (pintype "passive"))
    )
    (net (code "107") (name "Net-(Q4-PadB)") (class "Default")
      (node (ref "Q4") (pin "B") (pinfunction "B_B") (pintype "passive"))
      (node (ref "Q6") (pin "C") (pinfunction "C_C") (pintype "passive"))
      (node (ref "R2") (pin "1") (pinfunction "1_1") (pintype "passive"))
    )
    (net (code "108") (name "Net-(Q7-PadE)") (class "Default")
      (node (ref "Q7") (pin "E") (pinfunction "E_E") (pintype "passive"))
      (node (ref "Q8") (pin "E") (pinfunction "E_E") (pintype "passive"))
    )
    (net (code "109") (name "Net-(Q9-PadE)") (class "Default")
      (node (ref "Q9") (pin "E") (pinfunction "E_E") (pintype "passive"))
      (node (ref "R27") (pin "1") (pinfunction "1_1") (pintype "passive"))
    )
    (net (code "110") (name "Net-(Q10-PadB)") (class "Default")
      (node (ref "Q10") (pin "B") (pinfunction "B_B") (pintype "passive"))
      (node (ref "Q10") (pin "C") (pinfunction "C_C") (pintype "passive"))
      (node (ref "Q11") (pin "C") (pinfunction "C_C") (pintype "passive"))
      (node (ref "Q9") (pin "B") (pinfunction "B_B") (pintype "passive"))
    )
    (net (code "111") (name "Net-(Q10-PadE)") (class "Default")
      (node (ref "Q10") (pin "E") (pinfunction "E_E") (pintype "passive"))
      (node (ref "R26") (pin "1") (pinfunction "1_1") (pintype "passive"))
    )
    (net (code "112") (name "Net-(Q11-PadB)") (class "Default")
      (node (ref "Q11") (pin "B") (pinfunction "B_B") (pintype "passive"))
      (node (ref "Q12") (pin "B") (pinfunction "B_B") (pintype "passive"))
      (node (ref "Q12") (pin "C") (pinfunction "C_C") (pintype "passive"))
      (node (ref "R28") (pin "1") (pinfunction "1_1") (pintype "passive"))
    )
    (net (code "113") (name "Net-(Q13-PadB)") (class "Default")
      (node (ref "Q13") (pin "B") (pinfunction "B_B") (pintype "passive"))
      (node (ref "R31") (pin "2") (pinfunction "2_2") (pintype "passive"))
    )
    (net (code "114") (name "Net-(Q15-D)") (class "Default")
      (node (ref "Q15") (pin "3") (pinfunction "D_3") (pintype "passive"))
      (node (ref "R30") (pin "1") (pinfunction "1_1") (pintype "passive"))
    )
    (net (code "115") (name "Net-(R10-Pad2)") (class "Default")
      (node (ref "R10") (pin "2") (pinfunction "2_2") (pintype "passive"))
      (node (ref "R3") (pin "1") (pinfunction "1_1") (pintype "passive"))
      (node (ref "R4") (pin "2") (pinfunction "2_2") (pintype "passive"))
      (node (ref "R7") (pin "2") (pinfunction "2_2") (pintype "passive"))
      (node (ref "R8") (pin "2") (pinfunction "2_2") (pintype "passive"))
      (node (ref "R9") (pin "2") (pinfunction "2_2") (pintype "passive"))
    )
    (net (code "116") (name "Net-(U$1-PA4{slash}SPI1_NSS{slash}SPI3_NSS)") (class "Default")
      (node (ref "R69") (pin "1") (pinfunction "1_1") (pintype "passive"))
      (node (ref "U$1") (pin "P$29") (pinfunction "PA4/SPI1_NSS/SPI3_NSS_P$29") (pintype "bidirectional"))
    )
    (net (code "117") (name "Net-(U$1-PA5{slash}SPI1_SCK)") (class "Default")
      (node (ref "R70") (pin "1") (pinfunction "1_1") (pintype "passive"))
      (node (ref "U$1") (pin "P$30") (pinfunction "PA5/SPI1_SCK_P$30") (pintype "bidirectional"))
    )
    (net (code "118") (name "Net-(U$1-PA13{slash}SWDIO)") (class "Default")
      (node (ref "SWDIO") (pin "2") (pinfunction "2_2") (pintype "passive"))
      (node (ref "U$1") (pin "P$72") (pinfunction "PA13/SWDIO_P$72") (pintype "bidirectional"))
    )
    (net (code "119") (name "Net-(U$1-PA14{slash}SWCLK)") (class "Default")
      (node (ref "SWDIO") (pin "4") (pinfunction "4_4") (pintype "passive"))
      (node (ref "U$1") (pin "P$76") (pinfunction "PA14/SWCLK_P$76") (pintype "bidirectional"))
    )
    (net (code "120") (name "Net-(U$1-PB6{slash}I2C1_SCL{slash}USART1_TX{slash}CAN2_TX)") (class "Default")
      (node (ref "U$1") (pin "P$92") (pinfunction "PB6/I2C1_SCL/USART1_TX/CAN2_TX_P$92") (pintype "bidirectional"))
      (node (ref "UART") (pin "2") (pinfunction "2_2") (pintype "passive"))
    )
    (net (code "121") (name "Net-(U$1-PB7{slash}I2C1_SDA{slash}USART1_RX)") (class "Default")
      (node (ref "U$1") (pin "P$93") (pinfunction "PB7/I2C1_SDA/USART1_RX_P$93") (pintype "bidirectional"))
      (node (ref "UART") (pin "3") (pinfunction "3_3") (pintype "passive"))
    )
    (net (code "122") (name "Net-(U$1-PE15)") (class "Default")
      (node (ref "R71") (pin "2") (pinfunction "2_2") (pintype "passive"))
      (node (ref "U$1") (pin "P$46") (pinfunction "PE15_P$46") (pintype "bidirectional"))
    )
    (net (code "123") (name "Net-(U$1-PH0{slash}OSC_IN)") (class "Default")
      (node (ref "C16") (pin "2") (pinfunction "2_2") (pintype "passive"))
      (node (ref "U$1") (pin "P$12") (pinfunction "PH0/OSC_IN_P$12") (pintype "bidirectional"))
      (node (ref "Y1") (pin "3") (pinfunction "2_3") (pintype "passive"))
    )
    (net (code "124") (name "Net-(U$1-PH1{slash}OSC_OUT)") (class "Default")
      (node (ref "C15") (pin "2") (pinfunction "2_2") (pintype "passive"))
      (node (ref "U$1") (pin "P$13") (pinfunction "PH1/OSC_OUT_P$13") (pintype "bidirectional"))
      (node (ref "Y1") (pin "1") (pinfunction "1_1") (pintype "passive"))
    )
    (net (code "125") (name "Net-(U$1-VCAP_1)") (class "Default")
      (node (ref "C27") (pin "1") (pinfunction "1_1") (pintype "passive"))
      (node (ref "U$1") (pin "P$49") (pinfunction "VCAP_1_P$49") (pintype "bidirectional"))
    )
    (net (code "126") (name "Net-(U$1-VCAP_2)") (class "Default")
      (node (ref "C7") (pin "1") (pinfunction "1_1") (pintype "passive"))
      (node (ref "U$1") (pin "P$73") (pinfunction "VCAP_2_P$73") (pintype "bidirectional"))
    )
    (net (code "127") (name "Net-(U$1-VREF+)") (class "Default")
      (node (ref "C22") (pin "1") (pinfunction "1_1") (pintype "passive"))
      (node (ref "C29") (pin "1") (pinfunction "1_1") (pintype "passive"))
      (node (ref "R51") (pin "1") (pinfunction "1_1") (pintype "passive"))
      (node (ref "U$1") (pin "P$21") (pinfunction "VREF+_P$21") (pintype "bidirectional"))
    )
    (net (code "128") (name "OUTPUT_ENABLE") (class "Default")
      (node (ref "R31") (pin "1") (pinfunction "1_1") (pintype "passive"))
      (node (ref "U$1") (pin "P$5") (pinfunction "PE6_P$5") (pintype "bidirectional"))
    )
    (net (code "129") (name "PUSHPULL_OUT") (class "Default")
      (node (ref "C28") (pin "2") (pinfunction "2_2") (pintype "passive"))
      (node (ref "C6") (pin "2") (pinfunction "2_2") (pintype "passive"))
      (node (ref "K1") (pin "P") (pinfunction "P_P") (pintype "passive"))
      (node (ref "R11") (pin "2") (pinfunction "2_2") (pintype "passive"))
      (node (ref "R29") (pin "2") (pinfunction "2_2") (pintype "passive"))
      (node (ref "R60") (pin "1") (pinfunction "1_1") (pintype "passive"))
      (node (ref "R7") (pin "1") (pinfunction "1_1") (pintype "passive"))
      (node (ref "R8") (pin "1") (pinfunction "1_1") (pintype "passive"))
      (node (ref "R9") (pin "1") (pinfunction "1_1") (pintype "passive"))
    )
    (net (code "130") (name "SWITCH") (class "Default")
      (node (ref "S1") (pin "1") (pinfunction "P_1") (pintype "passive"))
      (node (ref "U$1") (pin "P$1") (pinfunction "PE2_P$1") (pintype "bidirectional"))
    )
    (net (code "131") (name "USBD_N") (class "Default")
      (node (ref "R64") (pin "2") (pinfunction "2_2") (pintype "passive"))
      (node (ref "U$1") (pin "P$70") (pinfunction "PA11/CAN1_RX_P$70") (pintype "bidirectional"))
    )
    (net (code "132") (name "USBD_P") (class "Default")
      (node (ref "R97") (pin "2") (pinfunction "2_2") (pintype "passive"))
      (node (ref "U$1") (pin "P$71") (pinfunction "PA12/CAN1_TX_P$71") (pintype "bidirectional"))
    )
    (net (code "133") (name "USB_ID") (class "Default")
      (node (ref "R100") (pin "2") (pinfunction "2_2") (pintype "passive"))
      (node (ref "U$1") (pin "P$69") (pinfunction "PA10/USART1_RX_P$69") (pintype "bidirectional"))
    )
    (net (code "134") (name "USB_VBUS") (class "Default")
      (node (ref "C10") (pin "1") (pinfunction "1_1") (pintype "passive"))
      (node (ref "R98") (pin "2") (pinfunction "2_2") (pintype "passive"))
      (node (ref "U$1") (pin "P$68") (pinfunction "PA9/USART1_TX_P$68") (pintype "bidirectional"))
    )
    (net (code "135") (name "VDDA") (class "Default")
      (node (ref "C30") (pin "1") (pinfunction "1_1") (pintype "passive"))
      (node (ref "C31") (pin "1") (pinfunction "1_1") (pintype "passive"))
      (node (ref "L2") (pin "2") (pinfunction "2_2") (pintype "passive"))
      (node (ref "R22") (pin "1") (pinfunction "1_1") (pintype "passive"))
      (node (ref "U$1") (pin "P$22") (pinfunction "VDDA_P$22") (pintype "bidirectional"))
    )
    (net (code "136") (name "VIN") (class "Default")
      (node (ref "C24") (pin "+") (pinfunction "+_+") (pintype "passive"))
      (node (ref "C34") (pin "2") (pinfunction "2_2") (pintype "passive"))
      (node (ref "C49") (pin "1") (pinfunction "1_1") (pintype "passive"))
      (node (ref "IC12") (pin "8") (pinfunction "VCC_8") (pintype "input"))
      (node (ref "IC8") (pin "2") (pinfunction "VIN_2") (pintype "power_in"))
      (node (ref "L9") (pin "1") (pinfunction "1_1") (pintype "passive"))
      (node (ref "PAD1") (pin "1") (pinfunction "P_1") (pintype "passive"))
    )
    (net (code "137") (name "VOLTAGE_CTRL") (class "Default")
      (node (ref "IC7") (pin "10") (pinfunction "+IN_10") (pintype "input"))
      (node (ref "R69") (pin "2") (pinfunction "2_2") (pintype "passive"))
    )
    (net (code "138") (name "VOLTAGE_RANGE_SEL") (class "Default")
      (node (ref "Q15") (pin "1") (pinfunction "G_1") (pintype "passive"))
      (node (ref "U$1") (pin "P$38") (pinfunction "PE7_P$38") (pintype "bidirectional"))
    )
    (net (code "139") (name "VOUT_HIGHSIDE") (class "Default")
      (node (ref "Q2") (pin "E") (pinfunction "E_E") (pintype "passive"))
      (node (ref "Q6") (pin "E") (pinfunction "E_E") (pintype "passive"))
      (node (ref "R1") (pin "1") (pinfunction "1_1") (pintype "passive"))
      (node (ref "R3") (pin "2") (pinfunction "2_2") (pintype "passive"))
      (node (ref "R40") (pin "1") (pinfunction "1_1") (pintype "passive"))
    )
    (net (code "140") (name "VSUPPLY_HIGHSIDE") (class "Default")
      (node (ref "C25") (pin "+") (pinfunction "+_+") (pintype "passive"))
      (node (ref "C26") (pin "+") (pinfunction "+_+") (pintype "passive"))
      (node (ref "L1") (pin "2") (pinfunction "2_2") (pintype "passive"))
      (node (ref "Q2") (pin "C") (pinfunction "C_C") (pintype "passive"))
      (node (ref "Q4") (pin "E") (pinfunction "E_E") (pintype "passive"))
      (node (ref "R2") (pin "2") (pinfunction "2_2") (pintype "passive"))
      (node (ref "R38") (pin "2") (pinfunction "2_2") (pintype "passive"))
      (node (ref "R58") (pin "1") (pinfunction "1_1") (pintype "passive"))
    )
    (net (code "141") (name "VSUPPLY_LOWSIDE") (class "Default")
      (node (ref "IC10") (pin "3") (pinfunction "+IN_3") (pintype "input"))
      (node (ref "Q1") (pin "C") (pinfunction "C_C") (pintype "passive"))
      (node (ref "Q3") (pin "E") (pinfunction "E_E") (pintype "passive"))
      (node (ref "R45") (pin "2") (pinfunction "2_2") (pintype "passive"))
      (node (ref "R6") (pin "2") (pinfunction "2_2") (pintype "passive"))
    )
    (net (code "142") (name "unconnected-(D9-C2-Pad2)") (class "Default")
      (node (ref "D9") (pin "2") (pinfunction "C2_2") (pintype "passive"))
    )
    (net (code "143") (name "unconnected-(IC1-ON1-Pad1)") (class "Default")
      (node (ref "IC1") (pin "1") (pinfunction "ON1_1") (pintype "passive"))
    )
    (net (code "144") (name "unconnected-(IC1-ON2-Pad8)") (class "Default")
      (node (ref "IC1") (pin "8") (pinfunction "ON2_8") (pintype "passive"))
    )
    (net (code "145") (name "unconnected-(IC1-OPT-Pad5)") (class "Default")
      (node (ref "IC1") (pin "5") (pinfunction "OPT_5") (pintype "passive"))
    )
    (net (code "146") (name "unconnected-(IC2-ON1-Pad1)") (class "Default")
      (node (ref "IC2") (pin "1") (pinfunction "ON1_1") (pintype "passive"))
    )
    (net (code "147") (name "unconnected-(IC2-ON2-Pad8)") (class "Default")
      (node (ref "IC2") (pin "8") (pinfunction "ON2_8") (pintype "passive"))
    )
    (net (code "148") (name "unconnected-(IC2-OPT-Pad5)") (class "Default")
      (node (ref "IC2") (pin "5") (pinfunction "OPT_5") (pintype "passive"))
    )
    (net (code "149") (name "unconnected-(IC5-ON1-Pad1)") (class "Default")
      (node (ref "IC5") (pin "1") (pinfunction "ON1_1") (pintype "passive"))
    )
    (net (code "150") (name "unconnected-(IC5-ON2-Pad8)") (class "Default")
      (node (ref "IC5") (pin "8") (pinfunction "ON2_8") (pintype "passive"))
    )
    (net (code "151") (name "unconnected-(IC5-OPT-Pad5)") (class "Default")
      (node (ref "IC5") (pin "5") (pinfunction "OPT_5") (pintype "passive"))
    )
    (net (code "152") (name "unconnected-(IC10-ON1-Pad1)") (class "Default")
      (node (ref "IC10") (pin "1") (pinfunction "ON1_1") (pintype "passive"))
    )
    (net (code "153") (name "unconnected-(IC10-ON2-Pad8)") (class "Default")
      (node (ref "IC10") (pin "8") (pinfunction "ON2_8") (pintype "passive"))
    )
    (net (code "154") (name "unconnected-(IC10-OPT-Pad5)") (class "Default")
      (node (ref "IC10") (pin "5") (pinfunction "OPT_5") (pintype "passive"))
    )
    (net (code "155") (name "unconnected-(IC12B-SYNC-Pad2)") (class "Default")
      (node (ref "IC12") (pin "2") (pinfunction "SYNC_2") (pintype "input"))
    )
    (net (code "156") (name "unconnected-(IC12B-VREF-Pad6)") (class "Default")
      (node (ref "IC12") (pin "6") (pinfunction "VREF_6") (pintype "input"))
    )
    (net (code "157") (name "unconnected-(K1-PadO)") (class "Default")
      (node (ref "K1") (pin "O") (pinfunction "O_O") (pintype "passive"))
    )
    (net (code "158") (name "unconnected-(U$1-PA6{slash}SPI1_MISO-PadP$31)") (class "Default")
      (node (ref "U$1") (pin "P$31") (pinfunction "PA6/SPI1_MISO_P$31") (pintype "bidirectional"))
    )
    (net (code "159") (name "unconnected-(U$1-PA7{slash}SPI1_MOSI-PadP$32)") (class "Default")
      (node (ref "U$1") (pin "P$32") (pinfunction "PA7/SPI1_MOSI_P$32") (pintype "bidirectional"))
    )
    (net (code "160") (name "unconnected-(U$1-PA8{slash}I2C3_SCL-PadP$67)") (class "Default")
      (node (ref "U$1") (pin "P$67") (pinfunction "PA8/I2C3_SCL_P$67") (pintype "bidirectional"))
    )
    (net (code "161") (name "unconnected-(U$1-PA15{slash}SPI1_NSS{slash}SPI3_NSS-PadP$77)") (class "Default")
      (node (ref "U$1") (pin "P$77") (pinfunction "PA15/SPI1_NSS/SPI3_NSS_P$77") (pintype "bidirectional"))
    )
    (net (code "162") (name "unconnected-(U$1-PB0-PadP$35)") (class "Default")
      (node (ref "U$1") (pin "P$35") (pinfunction "PB0_P$35") (pintype "bidirectional"))
    )
    (net (code "163") (name "unconnected-(U$1-PB1-PadP$36)") (class "Default")
      (node (ref "U$1") (pin "P$36") (pinfunction "PB1_P$36") (pintype "bidirectional"))
    )
    (net (code "164") (name "unconnected-(U$1-PB2-PadP$37)") (class "Default")
      (node (ref "U$1") (pin "P$37") (pinfunction "PB2_P$37") (pintype "bidirectional"))
    )
    (net (code "165") (name "unconnected-(U$1-PB10{slash}I2C2_SCL{slash}SPI2_SCK{slash}USART3_TX-PadP$47)") (class "Default")
      (node (ref "U$1") (pin "P$47") (pinfunction "PB10/I2C2_SCL/SPI2_SCK/USART3_TX_P$47") (pintype "bidirectional"))
    )
    (net (code "166") (name "unconnected-(U$1-PB11{slash}I2C2_SDA{slash}USART3_RX-PadP$48)") (class "Default")
      (node (ref "U$1") (pin "P$48") (pinfunction "PB11/I2C2_SDA/USART3_RX_P$48") (pintype "bidirectional"))
    )
    (net (code "167") (name "unconnected-(U$1-PB12{slash}SPI2_NSS{slash}CAN2_RX-PadP$51)") (class "Default")
      (node (ref "U$1") (pin "P$51") (pinfunction "PB12/SPI2_NSS/CAN2_RX_P$51") (pintype "bidirectional"))
    )
    (net (code "168") (name "unconnected-(U$1-PB13{slash}SPI2_SCK{slash}CAN2_TX-PadP$52)") (class "Default")
      (node (ref "U$1") (pin "P$52") (pinfunction "PB13/SPI2_SCK/CAN2_TX_P$52") (pintype "bidirectional"))
    )
    (net (code "169") (name "unconnected-(U$1-PB14{slash}SPI2_MISO-PadP$53)") (class "Default")
      (node (ref "U$1") (pin "P$53") (pinfunction "PB14/SPI2_MISO_P$53") (pintype "bidirectional"))
    )
    (net (code "170") (name "unconnected-(U$1-PB15{slash}SPI2_MOSI-PadP$54)") (class "Default")
      (node (ref "U$1") (pin "P$54") (pinfunction "PB15/SPI2_MOSI_P$54") (pintype "bidirectional"))
    )
    (net (code "171") (name "unconnected-(U$1-PC0-PadP$15)") (class "Default")
      (node (ref "U$1") (pin "P$15") (pinfunction "PC0_P$15") (pintype "bidirectional"))
    )
    (net (code "172") (name "unconnected-(U$1-PC1-PadP$16)") (class "Default")
      (node (ref "U$1") (pin "P$16") (pinfunction "PC1_P$16") (pintype "bidirectional"))
    )
    (net (code "173") (name "unconnected-(U$1-PC4-PadP$33)") (class "Default")
      (node (ref "U$1") (pin "P$33") (pinfunction "PC4_P$33") (pintype "bidirectional"))
    )
    (net (code "174") (name "unconnected-(U$1-PC5-PadP$34)") (class "Default")
      (node (ref "U$1") (pin "P$34") (pinfunction "PC5_P$34") (pintype "bidirectional"))
    )
    (net (code "175") (name "unconnected-(U$1-PC6{slash}USART6_TX-PadP$63)") (class "Default")
      (node (ref "U$1") (pin "P$63") (pinfunction "PC6/USART6_TX_P$63") (pintype "bidirectional"))
    )
    (net (code "176") (name "unconnected-(U$1-PC13-PadP$7)") (class "Default")
      (node (ref "U$1") (pin "P$7") (pinfunction "PC13_P$7") (pintype "bidirectional"))
    )
    (net (code "177") (name "unconnected-(U$1-PC14-PadP$8)") (class "Default")
      (node (ref "U$1") (pin "P$8") (pinfunction "PC14_P$8") (pintype "bidirectional"))
    )
    (net (code "178") (name "unconnected-(U$1-PC15-PadP$9)") (class "Default")
      (node (ref "U$1") (pin "P$9") (pinfunction "PC15_P$9") (pintype "bidirectional"))
    )
    (net (code "179") (name "unconnected-(U$1-PE1-PadP$98)") (class "Default")
      (node (ref "U$1") (pin "P$98") (pinfunction "PE1_P$98") (pintype "bidirectional"))
    )
    (net (code "180") (name "unconnected-(U$1-PE5-PadP$4)") (class "Default")
      (node (ref "U$1") (pin "P$4") (pinfunction "PE5_P$4") (pintype "bidirectional"))
    )
    (net (code "181") (name "unconnected-(U$1-PE8-PadP$39)") (class "Default")
      (node (ref "U$1") (pin "P$39") (pinfunction "PE8_P$39") (pintype "bidirectional"))
    )
    (net (code "182") (name "unconnected-(U$1-PE9-PadP$40)") (class "Default")
      (node (ref "U$1") (pin "P$40") (pinfunction "PE9_P$40") (pintype "bidirectional"))
    )
    (net (code "183") (name "unconnected-(U$1-PE10-PadP$41)") (class "Default")
      (node (ref "U$1") (pin "P$41") (pinfunction "PE10_P$41") (pintype "bidirectional"))
    )
  )
)
